# NOMIDI_Controller_006_clean.net
KiCad netlist of a schematic drawn in EAGLE
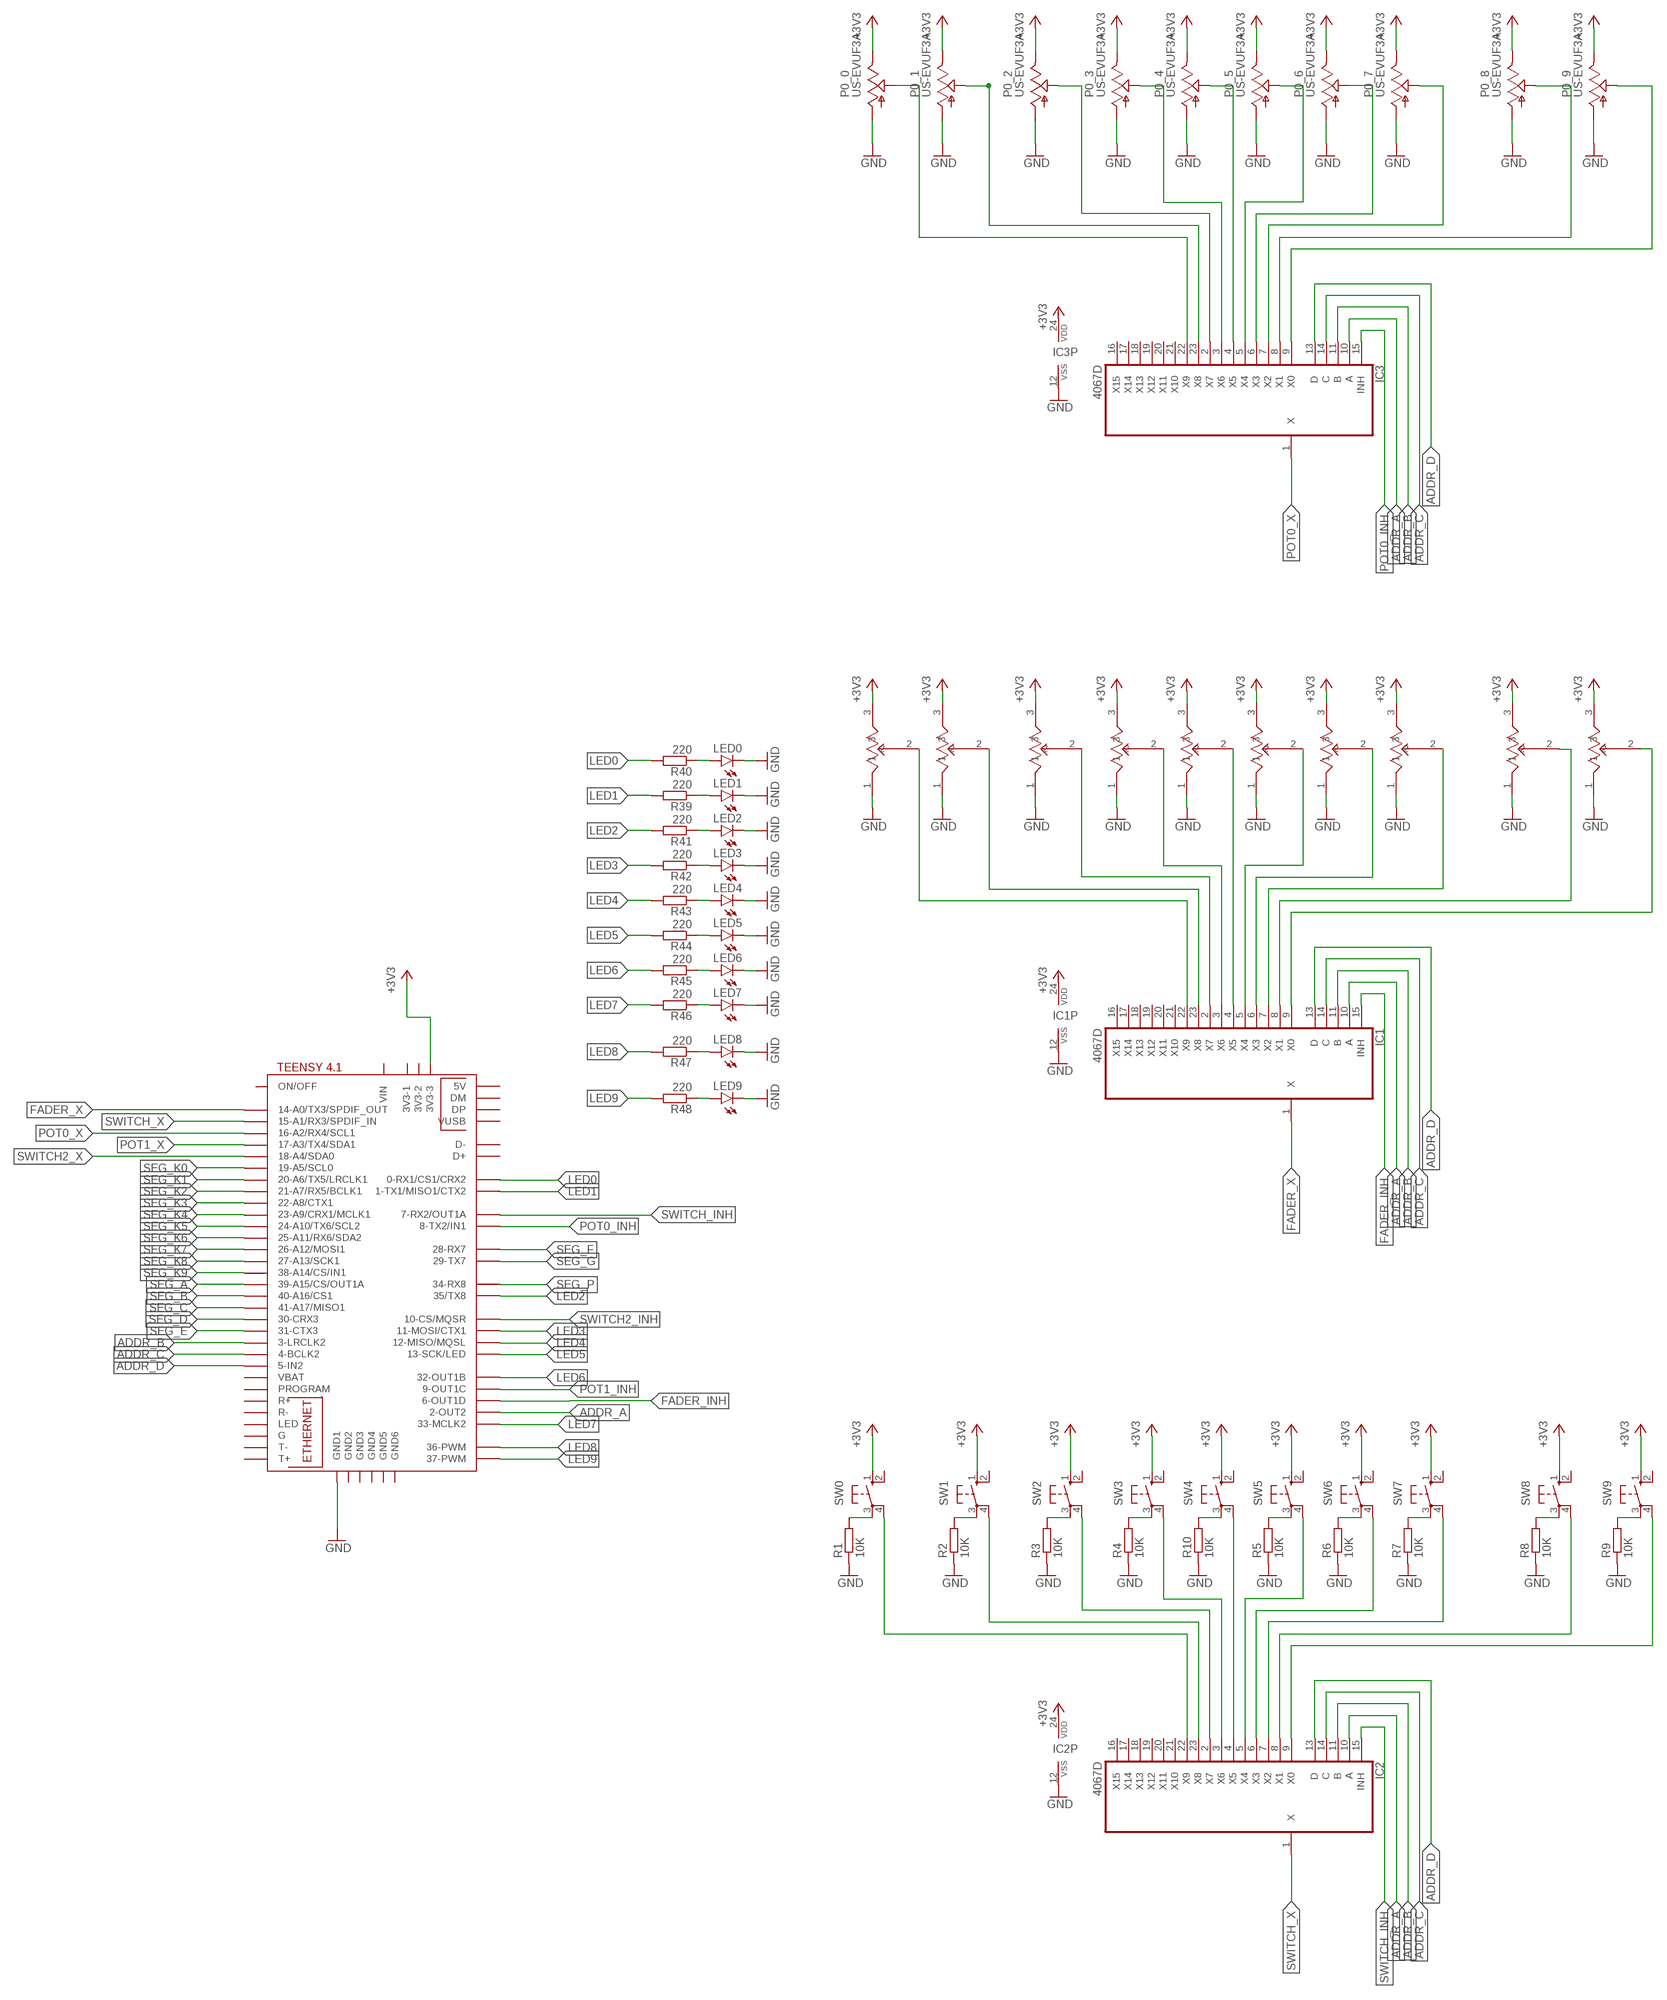
[diagram p0: schematic, sheet 1, part 1 of 3]
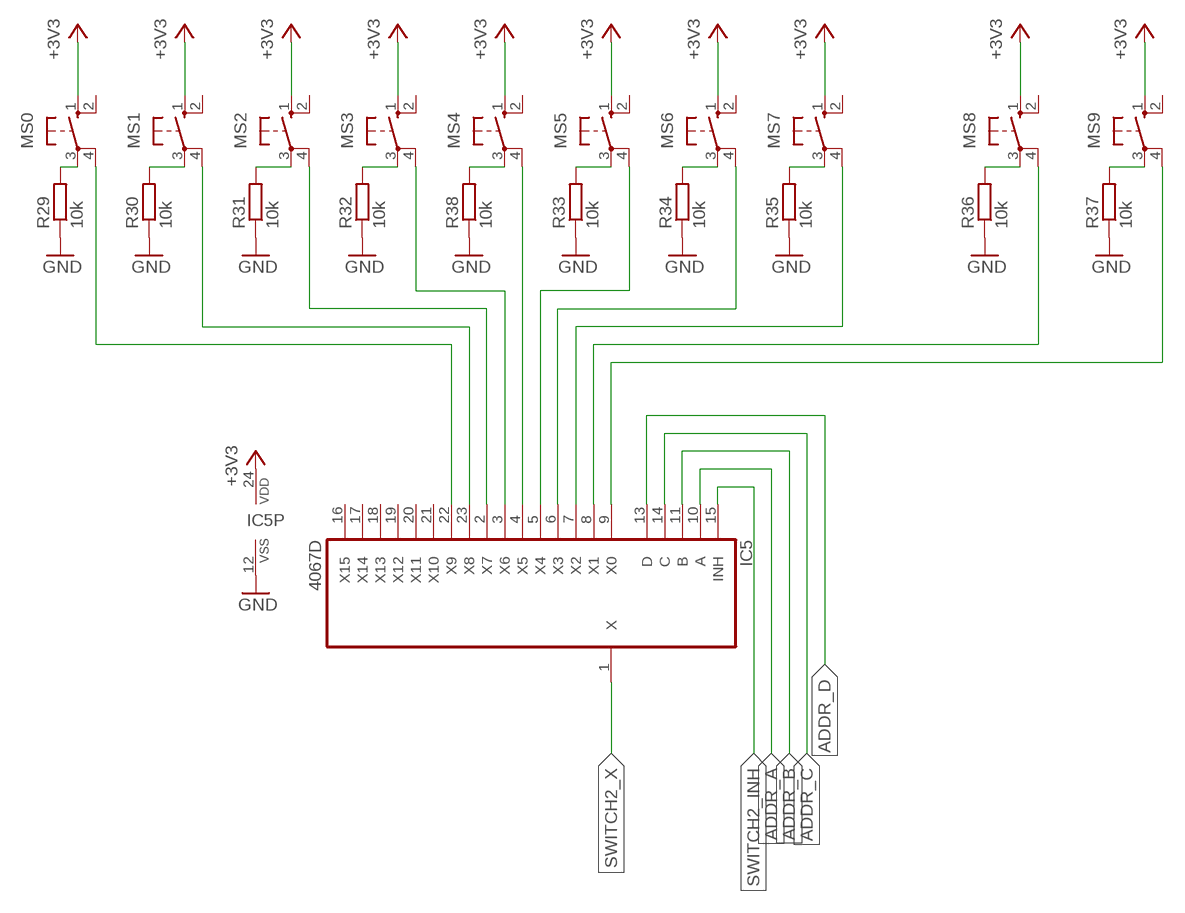
[diagram p1: schematic, sheet 1, part 2 of 3]
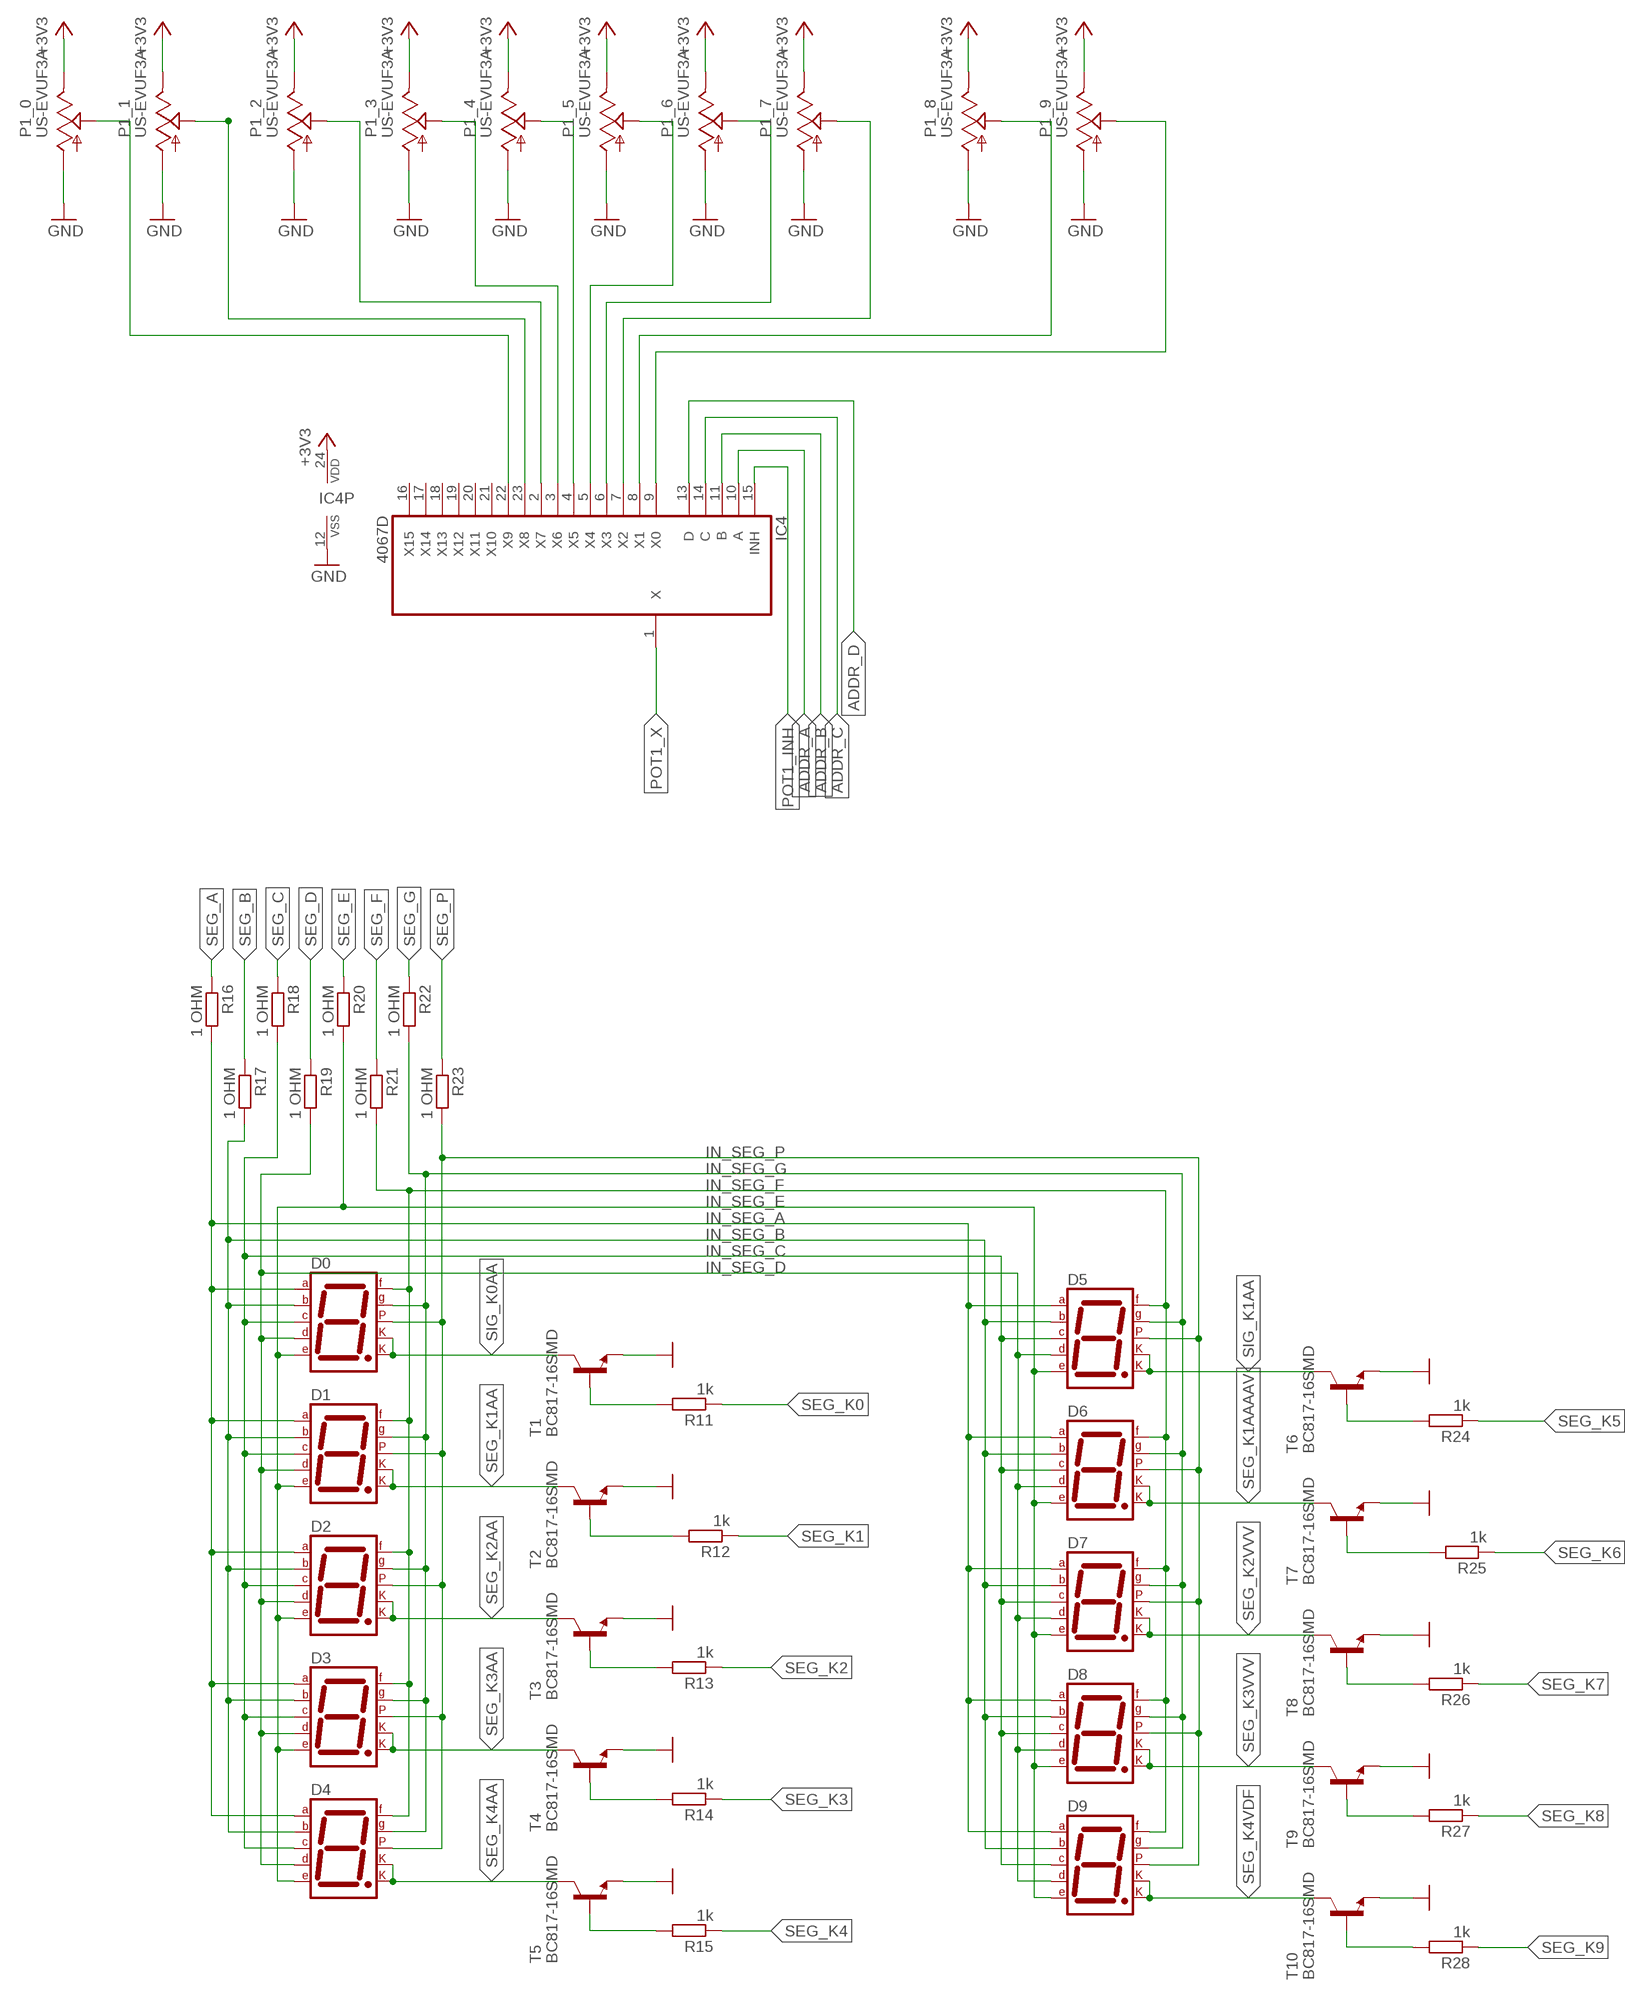
[diagram p2: schematic, sheet 1, part 3 of 3]

(export (version "E")
  (design (tool "Eeschema 10.0.6"))
  (components
    (comp (ref "D0")
      (value "7SEG-CK")
      (footprint "eagle-import:7SEG-13")
      (libsource (lib "eagle-import") (part "7SEG-CK"))
    )
    (comp (ref "D1")
      (value "7SEG-CK")
      (footprint "eagle-import:7SEG-13")
      (libsource (lib "eagle-import") (part "7SEG-CK"))
    )
    (comp (ref "D2")
      (value "7SEG-CK")
      (footprint "eagle-import:7SEG-13")
      (libsource (lib "eagle-import") (part "7SEG-CK"))
    )
    (comp (ref "D3")
      (value "7SEG-CK")
      (footprint "eagle-import:7SEG-13")
      (libsource (lib "eagle-import") (part "7SEG-CK"))
    )
    (comp (ref "D4")
      (value "7SEG-CK")
      (footprint "eagle-import:7SEG-13")
      (libsource (lib "eagle-import") (part "7SEG-CK"))
    )
    (comp (ref "D5")
      (value "7SEG-CK")
      (footprint "eagle-import:7SEG-13")
      (libsource (lib "eagle-import") (part "7SEG-CK"))
    )
    (comp (ref "D6")
      (value "7SEG-CK")
      (footprint "eagle-import:7SEG-13")
      (libsource (lib "eagle-import") (part "7SEG-CK"))
    )
    (comp (ref "D7")
      (value "7SEG-CK")
      (footprint "eagle-import:7SEG-13")
      (libsource (lib "eagle-import") (part "7SEG-CK"))
    )
    (comp (ref "D8")
      (value "7SEG-CK")
      (footprint "eagle-import:7SEG-13")
      (libsource (lib "eagle-import") (part "7SEG-CK"))
    )
    (comp (ref "D9")
      (value "7SEG-CK")
      (footprint "eagle-import:7SEG-13")
      (libsource (lib "eagle-import") (part "7SEG-CK"))
    )
    (comp (ref "IC1")
      (value "4067D")
      (footprint "eagle-import:SO24W")
      (libsource (lib "eagle-import") (part "4067D"))
    )
    (comp (ref "IC2")
      (value "4067D")
      (footprint "eagle-import:SO24W")
      (libsource (lib "eagle-import") (part "4067D"))
    )
    (comp (ref "IC3")
      (value "4067D")
      (footprint "eagle-import:SO24W")
      (libsource (lib "eagle-import") (part "4067D"))
    )
    (comp (ref "IC4")
      (value "4067D")
      (footprint "eagle-import:SO24W")
      (libsource (lib "eagle-import") (part "4067D"))
    )
    (comp (ref "IC5")
      (value "4067D")
      (footprint "eagle-import:SO24W")
      (libsource (lib "eagle-import") (part "4067D"))
    )
    (comp (ref "LED0")
      (value "LED3MM")
      (footprint "eagle-import:LED3MM")
      (libsource (lib "eagle-import") (part "LED3MM"))
    )
    (comp (ref "LED1")
      (value "LED3MM")
      (footprint "eagle-import:LED3MM")
      (libsource (lib "eagle-import") (part "LED3MM"))
    )
    (comp (ref "LED2")
      (value "LED3MM")
      (footprint "eagle-import:LED3MM")
      (libsource (lib "eagle-import") (part "LED3MM"))
    )
    (comp (ref "LED3")
      (value "LED3MM")
      (footprint "eagle-import:LED3MM")
      (libsource (lib "eagle-import") (part "LED3MM"))
    )
    (comp (ref "LED4")
      (value "LED3MM")
      (footprint "eagle-import:LED3MM")
      (libsource (lib "eagle-import") (part "LED3MM"))
    )
    (comp (ref "LED5")
      (value "LED3MM")
      (footprint "eagle-import:LED3MM")
      (libsource (lib "eagle-import") (part "LED3MM"))
    )
    (comp (ref "LED6")
      (value "LED3MM")
      (footprint "eagle-import:LED3MM")
      (libsource (lib "eagle-import") (part "LED3MM"))
    )
    (comp (ref "LED7")
      (value "LED3MM")
      (footprint "eagle-import:LED3MM")
      (libsource (lib "eagle-import") (part "LED3MM"))
    )
    (comp (ref "LED8")
      (value "LED3MM")
      (footprint "eagle-import:LED3MM")
      (libsource (lib "eagle-import") (part "LED3MM"))
    )
    (comp (ref "LED9")
      (value "LED3MM")
      (footprint "eagle-import:LED3MM")
      (libsource (lib "eagle-import") (part "LED3MM"))
    )
    (comp (ref "M0")
      (value "SLIDEPOT-ALPS-60MM")
      (footprint "eagle-import:RS6011SP600")
      (libsource (lib "eagle-import") (part "SLIDEPOT-ALPS-60MM"))
    )
    (comp (ref "M1")
      (value "SLIDEPOT-ALPS-60MM")
      (footprint "eagle-import:RS6011SP600")
      (libsource (lib "eagle-import") (part "SLIDEPOT-ALPS-60MM"))
    )
    (comp (ref "MS0")
      (value "10-XX")
      (footprint "eagle-import:B3F-10XX")
      (fields (field (name "MPN") "B3F-1000"))
      (libsource (lib "eagle-import") (part "10-XX"))
    )
    (comp (ref "MS1")
      (value "10-XX")
      (footprint "eagle-import:B3F-10XX")
      (fields (field (name "MPN") "B3F-1000"))
      (libsource (lib "eagle-import") (part "10-XX"))
    )
    (comp (ref "MS2")
      (value "10-XX")
      (footprint "eagle-import:B3F-10XX")
      (fields (field (name "MPN") "B3F-1000"))
      (libsource (lib "eagle-import") (part "10-XX"))
    )
    (comp (ref "MS3")
      (value "10-XX")
      (footprint "eagle-import:B3F-10XX")
      (fields (field (name "MPN") "B3F-1000"))
      (libsource (lib "eagle-import") (part "10-XX"))
    )
    (comp (ref "MS4")
      (value "10-XX")
      (footprint "eagle-import:B3F-10XX")
      (fields (field (name "MPN") "B3F-1000"))
      (libsource (lib "eagle-import") (part "10-XX"))
    )
    (comp (ref "MS5")
      (value "10-XX")
      (footprint "eagle-import:B3F-10XX")
      (fields (field (name "MPN") "B3F-1000"))
      (libsource (lib "eagle-import") (part "10-XX"))
    )
    (comp (ref "MS6")
      (value "10-XX")
      (footprint "eagle-import:B3F-10XX")
      (fields (field (name "MPN") "B3F-1000"))
      (libsource (lib "eagle-import") (part "10-XX"))
    )
    (comp (ref "MS7")
      (value "10-XX")
      (footprint "eagle-import:B3F-10XX")
      (fields (field (name "MPN") "B3F-1000"))
      (libsource (lib "eagle-import") (part "10-XX"))
    )
    (comp (ref "MS8")
      (value "10-XX")
      (footprint "eagle-import:B3F-10XX")
      (fields (field (name "MPN") "B3F-1000"))
      (libsource (lib "eagle-import") (part "10-XX"))
    )
    (comp (ref "MS9")
      (value "10-XX")
      (footprint "eagle-import:B3F-10XX")
      (fields (field (name "MPN") "B3F-1000"))
      (libsource (lib "eagle-import") (part "10-XX"))
    )
    (comp (ref "P0_0")
      (value "US-EVUF3A")
      (footprint "eagle-import:EVUF")
      (libsource (lib "eagle-import") (part "US-EVUAF3"))
    )
    (comp (ref "P0_1")
      (value "US-EVUF3A")
      (footprint "eagle-import:EVUF")
      (libsource (lib "eagle-import") (part "US-EVUAF3"))
    )
    (comp (ref "P0_2")
      (value "US-EVUF3A")
      (footprint "eagle-import:EVUF")
      (libsource (lib "eagle-import") (part "US-EVUAF3"))
    )
    (comp (ref "P0_3")
      (value "US-EVUF3A")
      (footprint "eagle-import:EVUF")
      (libsource (lib "eagle-import") (part "US-EVUAF3"))
    )
    (comp (ref "P0_4")
      (value "US-EVUF3A")
      (footprint "eagle-import:EVUF")
      (libsource (lib "eagle-import") (part "US-EVUAF3"))
    )
    (comp (ref "P0_5")
      (value "US-EVUF3A")
      (footprint "eagle-import:EVUF")
      (libsource (lib "eagle-import") (part "US-EVUAF3"))
    )
    (comp (ref "P0_6")
      (value "US-EVUF3A")
      (footprint "eagle-import:EVUF")
      (libsource (lib "eagle-import") (part "US-EVUAF3"))
    )
    (comp (ref "P0_7")
      (value "US-EVUF3A")
      (footprint "eagle-import:EVUF")
      (libsource (lib "eagle-import") (part "US-EVUAF3"))
    )
    (comp (ref "P0_8")
      (value "US-EVUF3A")
      (footprint "eagle-import:EVUF")
      (libsource (lib "eagle-import") (part "US-EVUAF3"))
    )
    (comp (ref "P0_9")
      (value "US-EVUF3A")
      (footprint "eagle-import:EVUF")
      (libsource (lib "eagle-import") (part "US-EVUAF3"))
    )
    (comp (ref "P1_0")
      (value "US-EVUF3A")
      (footprint "eagle-import:EVUF")
      (libsource (lib "eagle-import") (part "US-EVUAF3"))
    )
    (comp (ref "P1_1")
      (value "US-EVUF3A")
      (footprint "eagle-import:EVUF")
      (libsource (lib "eagle-import") (part "US-EVUAF3"))
    )
    (comp (ref "P1_2")
      (value "US-EVUF3A")
      (footprint "eagle-import:EVUF")
      (libsource (lib "eagle-import") (part "US-EVUAF3"))
    )
    (comp (ref "P1_3")
      (value "US-EVUF3A")
      (footprint "eagle-import:EVUF")
      (libsource (lib "eagle-import") (part "US-EVUAF3"))
    )
    (comp (ref "P1_4")
      (value "US-EVUF3A")
      (footprint "eagle-import:EVUF")
      (libsource (lib "eagle-import") (part "US-EVUAF3"))
    )
    (comp (ref "P1_5")
      (value "US-EVUF3A")
      (footprint "eagle-import:EVUF")
      (libsource (lib "eagle-import") (part "US-EVUAF3"))
    )
    (comp (ref "P1_6")
      (value "US-EVUF3A")
      (footprint "eagle-import:EVUF")
      (libsource (lib "eagle-import") (part "US-EVUAF3"))
    )
    (comp (ref "P1_7")
      (value "US-EVUF3A")
      (footprint "eagle-import:EVUF")
      (libsource (lib "eagle-import") (part "US-EVUAF3"))
    )
    (comp (ref "P1_8")
      (value "US-EVUF3A")
      (footprint "eagle-import:EVUF")
      (libsource (lib "eagle-import") (part "US-EVUAF3"))
    )
    (comp (ref "P1_9")
      (value "US-EVUF3A")
      (footprint "eagle-import:EVUF")
      (libsource (lib "eagle-import") (part "US-EVUAF3"))
    )
    (comp (ref "R1")
      (value "10K")
      (footprint "eagle-import:0207_7")
      (libsource (lib "eagle-import") (part "R-EU_0207/7"))
    )
    (comp (ref "R2")
      (value "10K")
      (footprint "eagle-import:0207_7")
      (libsource (lib "eagle-import") (part "R-EU_0207/7"))
    )
    (comp (ref "R3")
      (value "10K")
      (footprint "eagle-import:0207_7")
      (libsource (lib "eagle-import") (part "R-EU_0207/7"))
    )
    (comp (ref "R4")
      (value "10K")
      (footprint "eagle-import:0207_7")
      (libsource (lib "eagle-import") (part "R-EU_0207/7"))
    )
    (comp (ref "R5")
      (value "10K")
      (footprint "eagle-import:0207_7")
      (libsource (lib "eagle-import") (part "R-EU_0207/7"))
    )
    (comp (ref "R6")
      (value "10K")
      (footprint "eagle-import:0207_7")
      (libsource (lib "eagle-import") (part "R-EU_0207/7"))
    )
    (comp (ref "R7")
      (value "10K")
      (footprint "eagle-import:0207_7")
      (libsource (lib "eagle-import") (part "R-EU_0207/7"))
    )
    (comp (ref "R8")
      (value "10K")
      (footprint "eagle-import:0207_7")
      (libsource (lib "eagle-import") (part "R-EU_0207/7"))
    )
    (comp (ref "R9")
      (value "10K")
      (footprint "eagle-import:0207_7")
      (libsource (lib "eagle-import") (part "R-EU_0207/7"))
    )
    (comp (ref "R10")
      (value "10K")
      (footprint "eagle-import:0207_7")
      (libsource (lib "eagle-import") (part "R-EU_0207/7"))
    )
    (comp (ref "R11")
      (value "1k")
      (footprint "eagle-import:0207_7")
      (libsource (lib "eagle-import") (part "R-EU_0207/7"))
    )
    (comp (ref "R12")
      (value "1k")
      (footprint "eagle-import:0207_7")
      (libsource (lib "eagle-import") (part "R-EU_0207/7"))
    )
    (comp (ref "R13")
      (value "1k")
      (footprint "eagle-import:0207_7")
      (libsource (lib "eagle-import") (part "R-EU_0207/7"))
    )
    (comp (ref "R14")
      (value "1k")
      (footprint "eagle-import:0207_7")
      (libsource (lib "eagle-import") (part "R-EU_0207/7"))
    )
    (comp (ref "R15")
      (value "1k")
      (footprint "eagle-import:0207_7")
      (libsource (lib "eagle-import") (part "R-EU_0207/7"))
    )
    (comp (ref "R16")
      (value "1 OHM")
      (footprint "eagle-import:0207_7")
      (libsource (lib "eagle-import") (part "R-EU_0207/7"))
    )
    (comp (ref "R17")
      (value "1 OHM")
      (footprint "eagle-import:0207_7")
      (libsource (lib "eagle-import") (part "R-EU_0207/7"))
    )
    (comp (ref "R18")
      (value "1 OHM")
      (footprint "eagle-import:0207_7")
      (libsource (lib "eagle-import") (part "R-EU_0207/7"))
    )
    (comp (ref "R19")
      (value "1 OHM")
      (footprint "eagle-import:0207_7")
      (libsource (lib "eagle-import") (part "R-EU_0207/7"))
    )
    (comp (ref "R20")
      (value "1 OHM")
      (footprint "eagle-import:0207_7")
      (libsource (lib "eagle-import") (part "R-EU_0207/7"))
    )
    (comp (ref "R21")
      (value "1 OHM")
      (footprint "eagle-import:0207_7")
      (libsource (lib "eagle-import") (part "R-EU_0207/7"))
    )
    (comp (ref "R22")
      (value "1 OHM")
      (footprint "eagle-import:0207_7")
      (libsource (lib "eagle-import") (part "R-EU_0207/7"))
    )
    (comp (ref "R23")
      (value "1 OHM")
      (footprint "eagle-import:0207_7")
      (libsource (lib "eagle-import") (part "R-EU_0207/7"))
    )
    (comp (ref "R24")
      (value "1k")
      (footprint "eagle-import:0207_7")
      (libsource (lib "eagle-import") (part "R-EU_0207/7"))
    )
    (comp (ref "R25")
      (value "1k")
      (footprint "eagle-import:0207_7")
      (libsource (lib "eagle-import") (part "R-EU_0207/7"))
    )
    (comp (ref "R26")
      (value "1k")
      (footprint "eagle-import:0207_7")
      (libsource (lib "eagle-import") (part "R-EU_0207/7"))
    )
    (comp (ref "R27")
      (value "1k")
      (footprint "eagle-import:0207_7")
      (libsource (lib "eagle-import") (part "R-EU_0207/7"))
    )
    (comp (ref "R28")
      (value "1k")
      (footprint "eagle-import:0207_7")
      (libsource (lib "eagle-import") (part "R-EU_0207/7"))
    )
    (comp (ref "R29")
      (value "10k")
      (footprint "eagle-import:0207_7")
      (libsource (lib "eagle-import") (part "R-EU_0207/7"))
    )
    (comp (ref "R30")
      (value "10k")
      (footprint "eagle-import:0207_7")
      (libsource (lib "eagle-import") (part "R-EU_0207/7"))
    )
    (comp (ref "R31")
      (value "10k")
      (footprint "eagle-import:0207_7")
      (libsource (lib "eagle-import") (part "R-EU_0207/7"))
    )
    (comp (ref "R32")
      (value "10k")
      (footprint "eagle-import:0207_7")
      (libsource (lib "eagle-import") (part "R-EU_0207/7"))
    )
    (comp (ref "R33")
      (value "10k")
      (footprint "eagle-import:0207_7")
      (libsource (lib "eagle-import") (part "R-EU_0207/7"))
    )
    (comp (ref "R34")
      (value "10k")
      (footprint "eagle-import:0207_7")
      (libsource (lib "eagle-import") (part "R-EU_0207/7"))
    )
    (comp (ref "R35")
      (value "10k")
      (footprint "eagle-import:0207_7")
      (libsource (lib "eagle-import") (part "R-EU_0207/7"))
    )
    (comp (ref "R36")
      (value "10k")
      (footprint "eagle-import:0207_7")
      (libsource (lib "eagle-import") (part "R-EU_0207/7"))
    )
    (comp (ref "R37")
      (value "10k")
      (footprint "eagle-import:0207_7")
      (libsource (lib "eagle-import") (part "R-EU_0207/7"))
    )
    (comp (ref "R38")
      (value "10k")
      (footprint "eagle-import:0207_7")
      (libsource (lib "eagle-import") (part "R-EU_0207/7"))
    )
    (comp (ref "R39")
      (value "220")
      (footprint "eagle-import:0207_7")
      (libsource (lib "eagle-import") (part "R-EU_0207/7"))
    )
    (comp (ref "R40")
      (value "220")
      (footprint "eagle-import:0207_7")
      (libsource (lib "eagle-import") (part "R-EU_0207/7"))
    )
    (comp (ref "R41")
      (value "220")
      (footprint "eagle-import:0207_7")
      (libsource (lib "eagle-import") (part "R-EU_0207/7"))
    )
    (comp (ref "R42")
      (value "220")
      (footprint "eagle-import:0207_7")
      (libsource (lib "eagle-import") (part "R-EU_0207/7"))
    )
    (comp (ref "R43")
      (value "220")
      (footprint "eagle-import:0207_7")
      (libsource (lib "eagle-import") (part "R-EU_0207/7"))
    )
    (comp (ref "R44")
      (value "220")
      (footprint "eagle-import:0207_7")
      (libsource (lib "eagle-import") (part "R-EU_0207/7"))
    )
    (comp (ref "R45")
      (value "220")
      (footprint "eagle-import:0207_7")
      (libsource (lib "eagle-import") (part "R-EU_0207/7"))
    )
    (comp (ref "R46")
      (value "220")
      (footprint "eagle-import:0207_7")
      (libsource (lib "eagle-import") (part "R-EU_0207/7"))
    )
    (comp (ref "R47")
      (value "220")
      (footprint "eagle-import:0207_7")
      (libsource (lib "eagle-import") (part "R-EU_0207/7"))
    )
    (comp (ref "R48")
      (value "220")
      (footprint "eagle-import:0207_7")
      (libsource (lib "eagle-import") (part "R-EU_0207/7"))
    )
    (comp (ref "S0")
      (value "SLIDEPOT-ALPS-60MM")
      (footprint "eagle-import:RS6011SP600")
      (libsource (lib "eagle-import") (part "SLIDEPOT-ALPS-60MM"))
    )
    (comp (ref "S1")
      (value "SLIDEPOT-ALPS-60MM")
      (footprint "eagle-import:RS6011SP600")
      (libsource (lib "eagle-import") (part "SLIDEPOT-ALPS-60MM"))
    )
    (comp (ref "S2")
      (value "SLIDEPOT-ALPS-60MM")
      (footprint "eagle-import:RS6011SP600")
      (libsource (lib "eagle-import") (part "SLIDEPOT-ALPS-60MM"))
    )
    (comp (ref "S3")
      (value "SLIDEPOT-ALPS-60MM")
      (footprint "eagle-import:RS6011SP600")
      (libsource (lib "eagle-import") (part "SLIDEPOT-ALPS-60MM"))
    )
    (comp (ref "S4")
      (value "SLIDEPOT-ALPS-60MM")
      (footprint "eagle-import:RS6011SP600")
      (libsource (lib "eagle-import") (part "SLIDEPOT-ALPS-60MM"))
    )
    (comp (ref "S5")
      (value "SLIDEPOT-ALPS-60MM")
      (footprint "eagle-import:RS6011SP600")
      (libsource (lib "eagle-import") (part "SLIDEPOT-ALPS-60MM"))
    )
    (comp (ref "S6")
      (value "SLIDEPOT-ALPS-60MM")
      (footprint "eagle-import:RS6011SP600")
      (libsource (lib "eagle-import") (part "SLIDEPOT-ALPS-60MM"))
    )
    (comp (ref "S7")
      (value "SLIDEPOT-ALPS-60MM")
      (footprint "eagle-import:RS6011SP600")
      (libsource (lib "eagle-import") (part "SLIDEPOT-ALPS-60MM"))
    )
    (comp (ref "SW0")
      (value "10-XX")
      (footprint "eagle-import:B3F-10XX")
      (fields (field (name "MPN") "B3F-1000"))
      (libsource (lib "eagle-import") (part "10-XX"))
    )
    (comp (ref "SW1")
      (value "10-XX")
      (footprint "eagle-import:B3F-10XX")
      (fields (field (name "MPN") "B3F-1000"))
      (libsource (lib "eagle-import") (part "10-XX"))
    )
    (comp (ref "SW2")
      (value "10-XX")
      (footprint "eagle-import:B3F-10XX")
      (fields (field (name "MPN") "B3F-1000"))
      (libsource (lib "eagle-import") (part "10-XX"))
    )
    (comp (ref "SW3")
      (value "10-XX")
      (footprint "eagle-import:B3F-10XX")
      (fields (field (name "MPN") "B3F-1000"))
      (libsource (lib "eagle-import") (part "10-XX"))
    )
    (comp (ref "SW4")
      (value "10-XX")
      (footprint "eagle-import:B3F-10XX")
      (fields (field (name "MPN") "B3F-1000"))
      (libsource (lib "eagle-import") (part "10-XX"))
    )
    (comp (ref "SW5")
      (value "10-XX")
      (footprint "eagle-import:B3F-10XX")
      (fields (field (name "MPN") "B3F-1000"))
      (libsource (lib "eagle-import") (part "10-XX"))
    )
    (comp (ref "SW6")
      (value "10-XX")
      (footprint "eagle-import:B3F-10XX")
      (fields (field (name "MPN") "B3F-1000"))
      (libsource (lib "eagle-import") (part "10-XX"))
    )
    (comp (ref "SW7")
      (value "10-XX")
      (footprint "eagle-import:B3F-10XX")
      (fields (field (name "MPN") "B3F-1000"))
      (libsource (lib "eagle-import") (part "10-XX"))
    )
    (comp (ref "SW8")
      (value "10-XX")
      (footprint "eagle-import:B3F-10XX")
      (fields (field (name "MPN") "B3F-1000"))
      (libsource (lib "eagle-import") (part "10-XX"))
    )
    (comp (ref "SW9")
      (value "10-XX")
      (footprint "eagle-import:B3F-10XX")
      (fields (field (name "MPN") "B3F-1000"))
      (libsource (lib "eagle-import") (part "10-XX"))
    )
    (comp (ref "T1")
      (value "BC817-16SMD")
      (footprint "eagle-import:SOT23-BEC")
      (libsource (lib "eagle-import") (part "BC817SMD-16"))
    )
    (comp (ref "T2")
      (value "BC817-16SMD")
      (footprint "eagle-import:SOT23-BEC")
      (libsource (lib "eagle-import") (part "BC817SMD-16"))
    )
    (comp (ref "T3")
      (value "BC817-16SMD")
      (footprint "eagle-import:SOT23-BEC")
      (libsource (lib "eagle-import") (part "BC817SMD-16"))
    )
    (comp (ref "T4")
      (value "BC817-16SMD")
      (footprint "eagle-import:SOT23-BEC")
      (libsource (lib "eagle-import") (part "BC817SMD-16"))
    )
    (comp (ref "T5")
      (value "BC817-16SMD")
      (footprint "eagle-import:SOT23-BEC")
      (libsource (lib "eagle-import") (part "BC817SMD-16"))
    )
    (comp (ref "T6")
      (value "BC817-16SMD")
      (footprint "eagle-import:SOT23-BEC")
      (libsource (lib "eagle-import") (part "BC817SMD-16"))
    )
    (comp (ref "T7")
      (value "BC817-16SMD")
      (footprint "eagle-import:SOT23-BEC")
      (libsource (lib "eagle-import") (part "BC817SMD-16"))
    )
    (comp (ref "T8")
      (value "BC817-16SMD")
      (footprint "eagle-import:SOT23-BEC")
      (libsource (lib "eagle-import") (part "BC817SMD-16"))
    )
    (comp (ref "T9")
      (value "BC817-16SMD")
      (footprint "eagle-import:SOT23-BEC")
      (libsource (lib "eagle-import") (part "BC817SMD-16"))
    )
    (comp (ref "T10")
      (value "BC817-16SMD")
      (footprint "eagle-import:SOT23-BEC")
      (libsource (lib "eagle-import") (part "BC817SMD-16"))
    )
    (comp (ref "U$1")
      (value "TEENSY41")
      (footprint "eagle-import:TEENSY41")
      (libsource (lib "eagle-import") (part "TEENSY41"))
    )
  )
  (nets
    (net (code "1") (name "+3V3") (class "Default")
      (node (ref "IC1") (pin "24") (pinfunction "VDD_24") (pintype "power_in"))
      (node (ref "IC2") (pin "24") (pinfunction "VDD_24") (pintype "power_in"))
      (node (ref "IC3") (pin "24") (pinfunction "VDD_24") (pintype "power_in"))
      (node (ref "IC4") (pin "24") (pinfunction "VDD_24") (pintype "power_in"))
      (node (ref "IC5") (pin "24") (pinfunction "VDD_24") (pintype "power_in"))
      (node (ref "M0") (pin "3") (pinfunction "3_3") (pintype "bidirectional"))
      (node (ref "M1") (pin "3") (pinfunction "3_3") (pintype "bidirectional"))
      (node (ref "MS0") (pin "1") (pinfunction "S_1") (pintype "passive"))
      (node (ref "MS1") (pin "1") (pinfunction "S_1") (pintype "passive"))
      (node (ref "MS2") (pin "1") (pinfunction "S_1") (pintype "passive"))
      (node (ref "MS3") (pin "1") (pinfunction "S_1") (pintype "passive"))
      (node (ref "MS4") (pin "1") (pinfunction "S_1") (pintype "passive"))
      (node (ref "MS5") (pin "1") (pinfunction "S_1") (pintype "passive"))
      (node (ref "MS6") (pin "1") (pinfunction "S_1") (pintype "passive"))
      (node (ref "MS7") (pin "1") (pinfunction "S_1") (pintype "passive"))
      (node (ref "MS8") (pin "1") (pinfunction "S_1") (pintype "passive"))
      (node (ref "MS9") (pin "1") (pinfunction "S_1") (pintype "passive"))
      (node (ref "P0_0") (pin "3") (pinfunction "E_3") (pintype "passive"))
      (node (ref "P0_1") (pin "3") (pinfunction "E_3") (pintype "passive"))
      (node (ref "P0_2") (pin "3") (pinfunction "E_3") (pintype "passive"))
      (node (ref "P0_3") (pin "3") (pinfunction "E_3") (pintype "passive"))
      (node (ref "P0_4") (pin "3") (pinfunction "E_3") (pintype "passive"))
      (node (ref "P0_5") (pin "3") (pinfunction "E_3") (pintype "passive"))
      (node (ref "P0_6") (pin "3") (pinfunction "E_3") (pintype "passive"))
      (node (ref "P0_7") (pin "3") (pinfunction "E_3") (pintype "passive"))
      (node (ref "P0_8") (pin "3") (pinfunction "E_3") (pintype "passive"))
      (node (ref "P0_9") (pin "3") (pinfunction "E_3") (pintype "passive"))
      (node (ref "P1_0") (pin "3") (pinfunction "E_3") (pintype "passive"))
      (node (ref "P1_1") (pin "3") (pinfunction "E_3") (pintype "passive"))
      (node (ref "P1_2") (pin "3") (pinfunction "E_3") (pintype "passive"))
      (node (ref "P1_3") (pin "3") (pinfunction "E_3") (pintype "passive"))
      (node (ref "P1_4") (pin "3") (pinfunction "E_3") (pintype "passive"))
      (node (ref "P1_5") (pin "3") (pinfunction "E_3") (pintype "passive"))
      (node (ref "P1_6") (pin "3") (pinfunction "E_3") (pintype "passive"))
      (node (ref "P1_7") (pin "3") (pinfunction "E_3") (pintype "passive"))
      (node (ref "P1_8") (pin "3") (pinfunction "E_3") (pintype "passive"))
      (node (ref "P1_9") (pin "3") (pinfunction "E_3") (pintype "passive"))
      (node (ref "S0") (pin "3") (pinfunction "3_3") (pintype "bidirectional"))
      (node (ref "S1") (pin "3") (pinfunction "3_3") (pintype "bidirectional"))
      (node (ref "S2") (pin "3") (pinfunction "3_3") (pintype "bidirectional"))
      (node (ref "S3") (pin "3") (pinfunction "3_3") (pintype "bidirectional"))
      (node (ref "S4") (pin "3") (pinfunction "3_3") (pintype "bidirectional"))
      (node (ref "S5") (pin "3") (pinfunction "3_3") (pintype "bidirectional"))
      (node (ref "S6") (pin "3") (pinfunction "3_3") (pintype "bidirectional"))
      (node (ref "S7") (pin "3") (pinfunction "3_3") (pintype "bidirectional"))
      (node (ref "SW0") (pin "1") (pinfunction "S_1") (pintype "passive"))
      (node (ref "SW1") (pin "1") (pinfunction "S_1") (pintype "passive"))
      (node (ref "SW2") (pin "1") (pinfunction "S_1") (pintype "passive"))
      (node (ref "SW3") (pin "1") (pinfunction "S_1") (pintype "passive"))
      (node (ref "SW4") (pin "1") (pinfunction "S_1") (pintype "passive"))
      (node (ref "SW5") (pin "1") (pinfunction "S_1") (pintype "passive"))
      (node (ref "SW6") (pin "1") (pinfunction "S_1") (pintype "passive"))
      (node (ref "SW7") (pin "1") (pinfunction "S_1") (pintype "passive"))
      (node (ref "SW8") (pin "1") (pinfunction "S_1") (pintype "passive"))
      (node (ref "SW9") (pin "1") (pinfunction "S_1") (pintype "passive"))
      (node (ref "U$1") (pin "3V3-3") (pinfunction "3V3-3_3V3-3") (pintype "bidirectional"))
    )
    (net (code "2") (name "/IN_SEG_A") (class "Default")
      (node (ref "D0") (pin "7") (pinfunction "A_7") (pintype "passive"))
      (node (ref "D1") (pin "7") (pinfunction "A_7") (pintype "passive"))
      (node (ref "D2") (pin "7") (pinfunction "A_7") (pintype "passive"))
      (node (ref "D3") (pin "7") (pinfunction "A_7") (pintype "passive"))
      (node (ref "D4") (pin "7") (pinfunction "A_7") (pintype "passive"))
      (node (ref "D5") (pin "7") (pinfunction "A_7") (pintype "passive"))
      (node (ref "D6") (pin "7") (pinfunction "A_7") (pintype "passive"))
      (node (ref "D7") (pin "7") (pinfunction "A_7") (pintype "passive"))
      (node (ref "D8") (pin "7") (pinfunction "A_7") (pintype "passive"))
      (node (ref "D9") (pin "7") (pinfunction "A_7") (pintype "passive"))
      (node (ref "R16") (pin "2") (pinfunction "2_2") (pintype "passive"))
    )
    (net (code "3") (name "/IN_SEG_B") (class "Default")
      (node (ref "D0") (pin "6") (pinfunction "B_6") (pintype "passive"))
      (node (ref "D1") (pin "6") (pinfunction "B_6") (pintype "passive"))
      (node (ref "D2") (pin "6") (pinfunction "B_6") (pintype "passive"))
      (node (ref "D3") (pin "6") (pinfunction "B_6") (pintype "passive"))
      (node (ref "D4") (pin "6") (pinfunction "B_6") (pintype "passive"))
      (node (ref "D5") (pin "6") (pinfunction "B_6") (pintype "passive"))
      (node (ref "D6") (pin "6") (pinfunction "B_6") (pintype "passive"))
      (node (ref "D7") (pin "6") (pinfunction "B_6") (pintype "passive"))
      (node (ref "D8") (pin "6") (pinfunction "B_6") (pintype "passive"))
      (node (ref "D9") (pin "6") (pinfunction "B_6") (pintype "passive"))
      (node (ref "R17") (pin "2") (pinfunction "2_2") (pintype "passive"))
    )
    (net (code "4") (name "/IN_SEG_C") (class "Default")
      (node (ref "D0") (pin "4") (pinfunction "C_4") (pintype "passive"))
      (node (ref "D1") (pin "4") (pinfunction "C_4") (pintype "passive"))
      (node (ref "D2") (pin "4") (pinfunction "C_4") (pintype "passive"))
      (node (ref "D3") (pin "4") (pinfunction "C_4") (pintype "passive"))
      (node (ref "D4") (pin "4") (pinfunction "C_4") (pintype "passive"))
      (node (ref "D5") (pin "4") (pinfunction "C_4") (pintype "passive"))
      (node (ref "D6") (pin "4") (pinfunction "C_4") (pintype "passive"))
      (node (ref "D7") (pin "4") (pinfunction "C_4") (pintype "passive"))
      (node (ref "D8") (pin "4") (pinfunction "C_4") (pintype "passive"))
      (node (ref "D9") (pin "4") (pinfunction "C_4") (pintype "passive"))
      (node (ref "R18") (pin "2") (pinfunction "2_2") (pintype "passive"))
    )
    (net (code "5") (name "/IN_SEG_D") (class "Default")
      (node (ref "D0") (pin "2") (pinfunction "D_2") (pintype "passive"))
      (node (ref "D1") (pin "2") (pinfunction "D_2") (pintype "passive"))
      (node (ref "D2") (pin "2") (pinfunction "D_2") (pintype "passive"))
      (node (ref "D3") (pin "2") (pinfunction "D_2") (pintype "passive"))
      (node (ref "D4") (pin "2") (pinfunction "D_2") (pintype "passive"))
      (node (ref "D5") (pin "2") (pinfunction "D_2") (pintype "passive"))
      (node (ref "D6") (pin "2") (pinfunction "D_2") (pintype "passive"))
      (node (ref "D7") (pin "2") (pinfunction "D_2") (pintype "passive"))
      (node (ref "D8") (pin "2") (pinfunction "D_2") (pintype "passive"))
      (node (ref "D9") (pin "2") (pinfunction "D_2") (pintype "passive"))
      (node (ref "R19") (pin "2") (pinfunction "2_2") (pintype "passive"))
    )
    (net (code "6") (name "/IN_SEG_E") (class "Default")
      (node (ref "D0") (pin "1") (pinfunction "E_1") (pintype "passive"))
      (node (ref "D1") (pin "1") (pinfunction "E_1") (pintype "passive"))
      (node (ref "D2") (pin "1") (pinfunction "E_1") (pintype "passive"))
      (node (ref "D3") (pin "1") (pinfunction "E_1") (pintype "passive"))
      (node (ref "D4") (pin "1") (pinfunction "E_1") (pintype "passive"))
      (node (ref "D5") (pin "1") (pinfunction "E_1") (pintype "passive"))
      (node (ref "D6") (pin "1") (pinfunction "E_1") (pintype "passive"))
      (node (ref "D7") (pin "1") (pinfunction "E_1") (pintype "passive"))
      (node (ref "D8") (pin "1") (pinfunction "E_1") (pintype "passive"))
      (node (ref "D9") (pin "1") (pinfunction "E_1") (pintype "passive"))
      (node (ref "R20") (pin "2") (pinfunction "2_2") (pintype "passive"))
    )
    (net (code "7") (name "/IN_SEG_F") (class "Default")
      (node (ref "D0") (pin "9") (pinfunction "F_9") (pintype "passive"))
      (node (ref "D1") (pin "9") (pinfunction "F_9") (pintype "passive"))
      (node (ref "D2") (pin "9") (pinfunction "F_9") (pintype "passive"))
      (node (ref "D3") (pin "9") (pinfunction "F_9") (pintype "passive"))
      (node (ref "D4") (pin "9") (pinfunction "F_9") (pintype "passive"))
      (node (ref "D5") (pin "9") (pinfunction "F_9") (pintype "passive"))
      (node (ref "D6") (pin "9") (pinfunction "F_9") (pintype "passive"))
      (node (ref "D7") (pin "9") (pinfunction "F_9") (pintype "passive"))
      (node (ref "D8") (pin "9") (pinfunction "F_9") (pintype "passive"))
      (node (ref "D9") (pin "9") (pinfunction "F_9") (pintype "passive"))
      (node (ref "R21") (pin "2") (pinfunction "2_2") (pintype "passive"))
    )
    (net (code "8") (name "/IN_SEG_G") (class "Default")
      (node (ref "D0") (pin "10") (pinfunction "G_10") (pintype "passive"))
      (node (ref "D1") (pin "10") (pinfunction "G_10") (pintype "passive"))
      (node (ref "D2") (pin "10") (pinfunction "G_10") (pintype "passive"))
      (node (ref "D3") (pin "10") (pinfunction "G_10") (pintype "passive"))
      (node (ref "D4") (pin "10") (pinfunction "G_10") (pintype "passive"))
      (node (ref "D5") (pin "10") (pinfunction "G_10") (pintype "passive"))
      (node (ref "D6") (pin "10") (pinfunction "G_10") (pintype "passive"))
      (node (ref "D7") (pin "10") (pinfunction "G_10") (pintype "passive"))
      (node (ref "D8") (pin "10") (pinfunction "G_10") (pintype "passive"))
      (node (ref "D9") (pin "10") (pinfunction "G_10") (pintype "passive"))
      (node (ref "R22") (pin "2") (pinfunction "2_2") (pintype "passive"))
    )
    (net (code "9") (name "/IN_SEG_P") (class "Default")
      (node (ref "D0") (pin "5") (pinfunction "DP_5") (pintype "passive"))
      (node (ref "D1") (pin "5") (pinfunction "DP_5") (pintype "passive"))
      (node (ref "D2") (pin "5") (pinfunction "DP_5") (pintype "passive"))
      (node (ref "D3") (pin "5") (pinfunction "DP_5") (pintype "passive"))
      (node (ref "D4") (pin "5") (pinfunction "DP_5") (pintype "passive"))
      (node (ref "D5") (pin "5") (pinfunction "DP_5") (pintype "passive"))
      (node (ref "D6") (pin "5") (pinfunction "DP_5") (pintype "passive"))
      (node (ref "D7") (pin "5") (pinfunction "DP_5") (pintype "passive"))
      (node (ref "D8") (pin "5") (pinfunction "DP_5") (pintype "passive"))
      (node (ref "D9") (pin "5") (pinfunction "DP_5") (pintype "passive"))
      (node (ref "R23") (pin "2") (pinfunction "2_2") (pintype "passive"))
    )
    (net (code "10") (name "ADDR_A") (class "Default")
      (node (ref "IC1") (pin "10") (pinfunction "A_10") (pintype "input"))
      (node (ref "IC2") (pin "10") (pinfunction "A_10") (pintype "input"))
      (node (ref "IC3") (pin "10") (pinfunction "A_10") (pintype "input"))
      (node (ref "IC4") (pin "10") (pinfunction "A_10") (pintype "input"))
      (node (ref "IC5") (pin "10") (pinfunction "A_10") (pintype "input"))
      (node (ref "U$1") (pin "2-OUT2") (pinfunction "2-OUT2_2-OUT2") (pintype "bidirectional"))
    )
    (net (code "11") (name "ADDR_B") (class "Default")
      (node (ref "IC1") (pin "11") (pinfunction "B_11") (pintype "input"))
      (node (ref "IC2") (pin "11") (pinfunction "B_11") (pintype "input"))
      (node (ref "IC3") (pin "11") (pinfunction "B_11") (pintype "input"))
      (node (ref "IC4") (pin "11") (pinfunction "B_11") (pintype "input"))
      (node (ref "IC5") (pin "11") (pinfunction "B_11") (pintype "input"))
      (node (ref "U$1") (pin "3-LRCLK2") (pinfunction "3-LRCLK2_3-LRCLK2") (pintype "bidirectional"))
    )
    (net (code "12") (name "ADDR_C") (class "Default")
      (node (ref "IC1") (pin "14") (pinfunction "C_14") (pintype "input"))
      (node (ref "IC2") (pin "14") (pinfunction "C_14") (pintype "input"))
      (node (ref "IC3") (pin "14") (pinfunction "C_14") (pintype "input"))
      (node (ref "IC4") (pin "14") (pinfunction "C_14") (pintype "input"))
      (node (ref "IC5") (pin "14") (pinfunction "C_14") (pintype "input"))
      (node (ref "U$1") (pin "4-BCLK2") (pinfunction "4-BCLK2_4-BCLK2") (pintype "bidirectional"))
    )
    (net (code "13") (name "ADDR_D") (class "Default")
      (node (ref "IC1") (pin "13") (pinfunction "D_13") (pintype "input"))
      (node (ref "IC2") (pin "13") (pinfunction "D_13") (pintype "input"))
      (node (ref "IC3") (pin "13") (pinfunction "D_13") (pintype "input"))
      (node (ref "IC4") (pin "13") (pinfunction "D_13") (pintype "input"))
      (node (ref "IC5") (pin "13") (pinfunction "D_13") (pintype "input"))
      (node (ref "U$1") (pin "5-IN2") (pinfunction "5-IN2_5-IN2") (pintype "bidirectional"))
    )
    (net (code "14") (name "FADER_INH") (class "Default")
      (node (ref "IC1") (pin "15") (pinfunction "INH_15") (pintype "input"))
      (node (ref "U$1") (pin "6-OUT1D") (pinfunction "6-OUT1D_6-OUT1D") (pintype "bidirectional"))
    )
    (net (code "15") (name "FADER_X") (class "Default")
      (node (ref "IC1") (pin "1") (pinfunction "X_1") (pintype "output"))
      (node (ref "U$1") (pin "14-A0/TX3/SPDIF_OUT") (pinfunction "14-A0/TX3/SPDIF_OUT_14-A0/TX3/SPDIF_OUT") (pintype "bidirectional"))
    )
    (net (code "16") (name "GND") (class "Default")
      (node (ref "IC1") (pin "12") (pinfunction "VSS_12") (pintype "power_in"))
      (node (ref "IC2") (pin "12") (pinfunction "VSS_12") (pintype "power_in"))
      (node (ref "IC3") (pin "12") (pinfunction "VSS_12") (pintype "power_in"))
      (node (ref "IC4") (pin "12") (pinfunction "VSS_12") (pintype "power_in"))
      (node (ref "IC5") (pin "12") (pinfunction "VSS_12") (pintype "power_in"))
      (node (ref "LED0") (pin "K") (pinfunction "C_K") (pintype "passive"))
      (node (ref "LED1") (pin "K") (pinfunction "C_K") (pintype "passive"))
      (node (ref "LED2") (pin "K") (pinfunction "C_K") (pintype "passive"))
      (node (ref "LED3") (pin "K") (pinfunction "C_K") (pintype "passive"))
      (node (ref "LED4") (pin "K") (pinfunction "C_K") (pintype "passive"))
      (node (ref "LED5") (pin "K") (pinfunction "C_K") (pintype "passive"))
      (node (ref "LED6") (pin "K") (pinfunction "C_K") (pintype "passive"))
      (node (ref "LED7") (pin "K") (pinfunction "C_K") (pintype "passive"))
      (node (ref "LED8") (pin "K") (pinfunction "C_K") (pintype "passive"))
      (node (ref "LED9") (pin "K") (pinfunction "C_K") (pintype "passive"))
      (node (ref "M0") (pin "1") (pinfunction "1_1") (pintype "bidirectional"))
      (node (ref "M1") (pin "1") (pinfunction "1_1") (pintype "bidirectional"))
      (node (ref "P0_0") (pin "1") (pinfunction "A_1") (pintype "passive"))
      (node (ref "P0_1") (pin "1") (pinfunction "A_1") (pintype "passive"))
      (node (ref "P0_2") (pin "1") (pinfunction "A_1") (pintype "passive"))
      (node (ref "P0_3") (pin "1") (pinfunction "A_1") (pintype "passive"))
      (node (ref "P0_4") (pin "1") (pinfunction "A_1") (pintype "passive"))
      (node (ref "P0_5") (pin "1") (pinfunction "A_1") (pintype "passive"))
      (node (ref "P0_6") (pin "1") (pinfunction "A_1") (pintype "passive"))
      (node (ref "P0_7") (pin "1") (pinfunction "A_1") (pintype "passive"))
      (node (ref "P0_8") (pin "1") (pinfunction "A_1") (pintype "passive"))
      (node (ref "P0_9") (pin "1") (pinfunction "A_1") (pintype "passive"))
      (node (ref "P1_0") (pin "1") (pinfunction "A_1") (pintype "passive"))
      (node (ref "P1_1") (pin "1") (pinfunction "A_1") (pintype "passive"))
      (node (ref "P1_2") (pin "1") (pinfunction "A_1") (pintype "passive"))
      (node (ref "P1_3") (pin "1") (pinfunction "A_1") (pintype "passive"))
      (node (ref "P1_4") (pin "1") (pinfunction "A_1") (pintype "passive"))
      (node (ref "P1_5") (pin "1") (pinfunction "A_1") (pintype "passive"))
      (node (ref "P1_6") (pin "1") (pinfunction "A_1") (pintype "passive"))
      (node (ref "P1_7") (pin "1") (pinfunction "A_1") (pintype "passive"))
      (node (ref "P1_8") (pin "1") (pinfunction "A_1") (pintype "passive"))
      (node (ref "P1_9") (pin "1") (pinfunction "A_1") (pintype "passive"))
      (node (ref "R1") (pin "1") (pinfunction "1_1") (pintype "passive"))
      (node (ref "R10") (pin "1") (pinfunction "1_1") (pintype "passive"))
      (node (ref "R2") (pin "1") (pinfunction "1_1") (pintype "passive"))
      (node (ref "R29") (pin "1") (pinfunction "1_1") (pintype "passive"))
      (node (ref "R3") (pin "1") (pinfunction "1_1") (pintype "passive"))
      (node (ref "R30") (pin "1") (pinfunction "1_1") (pintype "passive"))
      (node (ref "R31") (pin "1") (pinfunction "1_1") (pintype "passive"))
      (node (ref "R32") (pin "1") (pinfunction "1_1") (pintype "passive"))
      (node (ref "R33") (pin "1") (pinfunction "1_1") (pintype "passive"))
      (node (ref "R34") (pin "1") (pinfunction "1_1") (pintype "passive"))
      (node (ref "R35") (pin "1") (pinfunction "1_1") (pintype "passive"))
      (node (ref "R36") (pin "1") (pinfunction "1_1") (pintype "passive"))
      (node (ref "R37") (pin "1") (pinfunction "1_1") (pintype "passive"))
      (node (ref "R38") (pin "1") (pinfunction "1_1") (pintype "passive"))
      (node (ref "R4") (pin "1") (pinfunction "1_1") (pintype "passive"))
      (node (ref "R5") (pin "1") (pinfunction "1_1") (pintype "passive"))
      (node (ref "R6") (pin "1") (pinfunction "1_1") (pintype "passive"))
      (node (ref "R7") (pin "1") (pinfunction "1_1") (pintype "passive"))
      (node (ref "R8") (pin "1") (pinfunction "1_1") (pintype "passive"))
      (node (ref "R9") (pin "1") (pinfunction "1_1") (pintype "passive"))
      (node (ref "S0") (pin "1") (pinfunction "1_1") (pintype "bidirectional"))
      (node (ref "S1") (pin "1") (pinfunction "1_1") (pintype "bidirectional"))
      (node (ref "S2") (pin "1") (pinfunction "1_1") (pintype "bidirectional"))
      (node (ref "S3") (pin "1") (pinfunction "1_1") (pintype "bidirectional"))
      (node (ref "S4") (pin "1") (pinfunction "1_1") (pintype "bidirectional"))
      (node (ref "S5") (pin "1") (pinfunction "1_1") (pintype "bidirectional"))
      (node (ref "S6") (pin "1") (pinfunction "1_1") (pintype "bidirectional"))
      (node (ref "S7") (pin "1") (pinfunction "1_1") (pintype "bidirectional"))
      (node (ref "T1") (pin "E") (pinfunction "E_E") (pintype "passive"))
      (node (ref "T10") (pin "E") (pinfunction "E_E") (pintype "passive"))
      (node (ref "T2") (pin "E") (pinfunction "E_E") (pintype "passive"))
      (node (ref "T3") (pin "E") (pinfunction "E_E") (pintype "passive"))
      (node (ref "T4") (pin "E") (pinfunction "E_E") (pintype "passive"))
      (node (ref "T5") (pin "E") (pinfunction "E_E") (pintype "passive"))
      (node (ref "T6") (pin "E") (pinfunction "E_E") (pintype "passive"))
      (node (ref "T7") (pin "E") (pinfunction "E_E") (pintype "passive"))
      (node (ref "T8") (pin "E") (pinfunction "E_E") (pintype "passive"))
      (node (ref "T9") (pin "E") (pinfunction "E_E") (pintype "passive"))
      (node (ref "U$1") (pin "GND1") (pinfunction "GND1_GND1") (pintype "bidirectional"))
    )
    (net (code "17") (name "LED0") (class "Default")
      (node (ref "R40") (pin "2") (pinfunction "2_2") (pintype "passive"))
      (node (ref "U$1") (pin "0-RX1/CS1/CRX2") (pinfunction "0-RX1/CS1/CRX2_0-RX1/CS1/CRX2") (pintype "bidirectional"))
    )
    (net (code "18") (name "LED1") (class "Default")
      (node (ref "R39") (pin "2") (pinfunction "2_2") (pintype "passive"))
      (node (ref "U$1") (pin "1-TX1/MISO1/CTX2") (pinfunction "1-TX1/MISO1/CTX2_1-TX1/MISO1/CTX2") (pintype "bidirectional"))
    )
    (net (code "19") (name "LED2") (class "Default")
      (node (ref "R41") (pin "2") (pinfunction "2_2") (pintype "passive"))
      (node (ref "U$1") (pin "35-TX8") (pinfunction "35/TX8_35-TX8") (pintype "bidirectional"))
    )
    (net (code "20") (name "LED3") (class "Default")
      (node (ref "R42") (pin "2") (pinfunction "2_2") (pintype "passive"))
      (node (ref "U$1") (pin "11-MOSI/CTX1") (pinfunction "11-MOSI/CTX1_11-MOSI/CTX1") (pintype "bidirectional"))
    )
    (net (code "21") (name "LED4") (class "Default")
      (node (ref "R43") (pin "2") (pinfunction "2_2") (pintype "passive"))
      (node (ref "U$1") (pin "12-MISO/MQSL") (pinfunction "12-MISO/MQSL_12-MISO/MQSL") (pintype "bidirectional"))
    )
    (net (code "22") (name "LED5") (class "Default")
      (node (ref "R44") (pin "2") (pinfunction "2_2") (pintype "passive"))
      (node (ref "U$1") (pin "13-SCK/LED") (pinfunction "13-SCK/LED_13-SCK/LED") (pintype "bidirectional"))
    )
    (net (code "23") (name "LED6") (class "Default")
      (node (ref "R45") (pin "2") (pinfunction "2_2") (pintype "passive"))
      (node (ref "U$1") (pin "32-OUT1B") (pinfunction "32-OUT1B_32-OUT1B") (pintype "bidirectional"))
    )
    (net (code "24") (name "LED7") (class "Default")
      (node (ref "R46") (pin "2") (pinfunction "2_2") (pintype "passive"))
      (node (ref "U$1") (pin "33-MCLK2") (pinfunction "33-MCLK2_33-MCLK2") (pintype "bidirectional"))
    )
    (net (code "25") (name "LED8") (class "Default")
      (node (ref "R47") (pin "2") (pinfunction "2_2") (pintype "passive"))
      (node (ref "U$1") (pin "36-PWM") (pinfunction "36-PWM_36-PWM") (pintype "bidirectional"))
    )
    (net (code "26") (name "LED9") (class "Default")
      (node (ref "R48") (pin "2") (pinfunction "2_2") (pintype "passive"))
      (node (ref "U$1") (pin "37-PWM") (pinfunction "37-PWM_37-PWM") (pintype "bidirectional"))
    )
    (net (code "27") (name "Net-(IC1A-X0)") (class "Default")
      (node (ref "IC1") (pin "9") (pinfunction "X0_9") (pintype "input"))
      (node (ref "M1") (pin "2") (pinfunction "2_2") (pintype "bidirectional"))
    )
    (net (code "28") (name "Net-(IC1A-X1)") (class "Default")
      (node (ref "IC1") (pin "8") (pinfunction "X1_8") (pintype "input"))
      (node (ref "M0") (pin "2") (pinfunction "2_2") (pintype "bidirectional"))
    )
    (net (code "29") (name "Net-(IC1A-X2)") (class "Default")
      (node (ref "IC1") (pin "7") (pinfunction "X2_7") (pintype "input"))
      (node (ref "S7") (pin "2") (pinfunction "2_2") (pintype "bidirectional"))
    )
    (net (code "30") (name "Net-(IC1A-X3)") (class "Default")
      (node (ref "IC1") (pin "6") (pinfunction "X3_6") (pintype "input"))
      (node (ref "S6") (pin "2") (pinfunction "2_2") (pintype "bidirectional"))
    )
    (net (code "31") (name "Net-(IC1A-X4)") (class "Default")
      (node (ref "IC1") (pin "5") (pinfunction "X4_5") (pintype "input"))
      (node (ref "S5") (pin "2") (pinfunction "2_2") (pintype "bidirectional"))
    )
    (net (code "32") (name "Net-(IC1A-X5)") (class "Default")
      (node (ref "IC1") (pin "4") (pinfunction "X5_4") (pintype "input"))
      (node (ref "S4") (pin "2") (pinfunction "2_2") (pintype "bidirectional"))
    )
    (net (code "33") (name "Net-(IC1A-X6)") (class "Default")
      (node (ref "IC1") (pin "3") (pinfunction "X6_3") (pintype "input"))
      (node (ref "S3") (pin "2") (pinfunction "2_2") (pintype "bidirectional"))
    )
    (net (code "34") (name "Net-(IC1A-X7)") (class "Default")
      (node (ref "IC1") (pin "2") (pinfunction "X7_2") (pintype "input"))
      (node (ref "S2") (pin "2") (pinfunction "2_2") (pintype "bidirectional"))
    )
    (net (code "35") (name "Net-(IC1A-X8)") (class "Default")
      (node (ref "IC1") (pin "23") (pinfunction "X8_23") (pintype "input"))
      (node (ref "S1") (pin "2") (pinfunction "2_2") (pintype "bidirectional"))
    )
    (net (code "36") (name "Net-(IC1A-X9)") (class "Default")
      (node (ref "IC1") (pin "22") (pinfunction "X9_22") (pintype "input"))
      (node (ref "S0") (pin "2") (pinfunction "2_2") (pintype "bidirectional"))
    )
    (net (code "37") (name "Net-(IC2A-X0)") (class "Default")
      (node (ref "IC2") (pin "9") (pinfunction "X0_9") (pintype "input"))
      (node (ref "SW9") (pin "4") (pinfunction "P1_4") (pintype "passive"))
    )
    (net (code "38") (name "Net-(IC2A-X1)") (class "Default")
      (node (ref "IC2") (pin "8") (pinfunction "X1_8") (pintype "input"))
      (node (ref "SW8") (pin "4") (pinfunction "P1_4") (pintype "passive"))
    )
    (net (code "39") (name "Net-(IC2A-X2)") (class "Default")
      (node (ref "IC2") (pin "7") (pinfunction "X2_7") (pintype "input"))
      (node (ref "SW7") (pin "4") (pinfunction "P1_4") (pintype "passive"))
    )
    (net (code "40") (name "Net-(IC2A-X3)") (class "Default")
      (node (ref "IC2") (pin "6") (pinfunction "X3_6") (pintype "input"))
      (node (ref "SW6") (pin "4") (pinfunction "P1_4") (pintype "passive"))
    )
    (net (code "41") (name "Net-(IC2A-X4)") (class "Default")
      (node (ref "IC2") (pin "5") (pinfunction "X4_5") (pintype "input"))
      (node (ref "SW5") (pin "4") (pinfunction "P1_4") (pintype "passive"))
    )
    (net (code "42") (name "Net-(IC2A-X5)") (class "Default")
      (node (ref "IC2") (pin "4") (pinfunction "X5_4") (pintype "input"))
      (node (ref "SW4") (pin "4") (pinfunction "P1_4") (pintype "passive"))
    )
    (net (code "43") (name "Net-(IC2A-X6)") (class "Default")
      (node (ref "IC2") (pin "3") (pinfunction "X6_3") (pintype "input"))
      (node (ref "SW3") (pin "4") (pinfunction "P1_4") (pintype "passive"))
    )
    (net (code "44") (name "Net-(IC2A-X7)") (class "Default")
      (node (ref "IC2") (pin "2") (pinfunction "X7_2") (pintype "input"))
      (node (ref "SW2") (pin "4") (pinfunction "P1_4") (pintype "passive"))
    )
    (net (code "45") (name "Net-(IC2A-X8)") (class "Default")
      (node (ref "IC2") (pin "23") (pinfunction "X8_23") (pintype "input"))
      (node (ref "SW1") (pin "4") (pinfunction "P1_4") (pintype "passive"))
    )
    (net (code "46") (name "Net-(IC2A-X9)") (class "Default")
      (node (ref "IC2") (pin "22") (pinfunction "X9_22") (pintype "input"))
      (node (ref "SW0") (pin "4") (pinfunction "P1_4") (pintype "passive"))
    )
    (net (code "47") (name "Net-(IC3A-X0)") (class "Default")
      (node (ref "IC3") (pin "9") (pinfunction "X0_9") (pintype "input"))
      (node (ref "P0_9") (pin "2") (pinfunction "S_2") (pintype "passive"))
    )
    (net (code "48") (name "Net-(IC3A-X1)") (class "Default")
      (node (ref "IC3") (pin "8") (pinfunction "X1_8") (pintype "input"))
      (node (ref "P0_8") (pin "2") (pinfunction "S_2") (pintype "passive"))
    )
    (net (code "49") (name "Net-(IC3A-X2)") (class "Default")
      (node (ref "IC3") (pin "7") (pinfunction "X2_7") (pintype "input"))
      (node (ref "P0_7") (pin "2") (pinfunction "S_2") (pintype "passive"))
    )
    (net (code "50") (name "Net-(IC3A-X3)") (class "Default")
      (node (ref "IC3") (pin "6") (pinfunction "X3_6") (pintype "input"))
      (node (ref "P0_6") (pin "2") (pinfunction "S_2") (pintype "passive"))
    )
    (net (code "51") (name "Net-(IC3A-X4)") (class "Default")
      (node (ref "IC3") (pin "5") (pinfunction "X4_5") (pintype "input"))
      (node (ref "P0_5") (pin "2") (pinfunction "S_2") (pintype "passive"))
    )
    (net (code "52") (name "Net-(IC3A-X5)") (class "Default")
      (node (ref "IC3") (pin "4") (pinfunction "X5_4") (pintype "input"))
      (node (ref "P0_4") (pin "2") (pinfunction "S_2") (pintype "passive"))
    )
    (net (code "53") (name "Net-(IC3A-X6)") (class "Default")
      (node (ref "IC3") (pin "3") (pinfunction "X6_3") (pintype "input"))
      (node (ref "P0_3") (pin "2") (pinfunction "S_2") (pintype "passive"))
    )
    (net (code "54") (name "Net-(IC3A-X7)") (class "Default")
      (node (ref "IC3") (pin "2") (pinfunction "X7_2") (pintype "input"))
      (node (ref "P0_2") (pin "2") (pinfunction "S_2") (pintype "passive"))
    )
    (net (code "55") (name "Net-(IC3A-X8)") (class "Default")
      (node (ref "IC3") (pin "23") (pinfunction "X8_23") (pintype "input"))
      (node (ref "P0_1") (pin "2") (pinfunction "S_2") (pintype "passive"))
    )
    (net (code "56") (name "Net-(IC3A-X9)") (class "Default")
      (node (ref "IC3") (pin "22") (pinfunction "X9_22") (pintype "input"))
      (node (ref "P0_0") (pin "2") (pinfunction "S_2") (pintype "passive"))
    )
    (net (code "57") (name "Net-(IC4A-X0)") (class "Default")
      (node (ref "IC4") (pin "9") (pinfunction "X0_9") (pintype "input"))
      (node (ref "P1_9") (pin "2") (pinfunction "S_2") (pintype "passive"))
    )
    (net (code "58") (name "Net-(IC4A-X1)") (class "Default")
      (node (ref "IC4") (pin "8") (pinfunction "X1_8") (pintype "input"))
      (node (ref "P1_8") (pin "2") (pinfunction "S_2") (pintype "passive"))
    )
    (net (code "59") (name "Net-(IC4A-X2)") (class "Default")
      (node (ref "IC4") (pin "7") (pinfunction "X2_7") (pintype "input"))
      (node (ref "P1_7") (pin "2") (pinfunction "S_2") (pintype "passive"))
    )
    (net (code "60") (name "Net-(IC4A-X3)") (class "Default")
      (node (ref "IC4") (pin "6") (pinfunction "X3_6") (pintype "input"))
      (node (ref "P1_6") (pin "2") (pinfunction "S_2") (pintype "passive"))
    )
    (net (code "61") (name "Net-(IC4A-X4)") (class "Default")
      (node (ref "IC4") (pin "5") (pinfunction "X4_5") (pintype "input"))
      (node (ref "P1_5") (pin "2") (pinfunction "S_2") (pintype "passive"))
    )
    (net (code "62") (name "Net-(IC4A-X5)") (class "Default")
      (node (ref "IC4") (pin "4") (pinfunction "X5_4") (pintype "input"))
      (node (ref "P1_4") (pin "2") (pinfunction "S_2") (pintype "passive"))
    )
    (net (code "63") (name "Net-(IC4A-X6)") (class "Default")
      (node (ref "IC4") (pin "3") (pinfunction "X6_3") (pintype "input"))
      (node (ref "P1_3") (pin "2") (pinfunction "S_2") (pintype "passive"))
    )
    (net (code "64") (name "Net-(IC4A-X7)") (class "Default")
      (node (ref "IC4") (pin "2") (pinfunction "X7_2") (pintype "input"))
      (node (ref "P1_2") (pin "2") (pinfunction "S_2") (pintype "passive"))
    )
    (net (code "65") (name "Net-(IC4A-X8)") (class "Default")
      (node (ref "IC4") (pin "23") (pinfunction "X8_23") (pintype "input"))
      (node (ref "P1_1") (pin "2") (pinfunction "S_2") (pintype "passive"))
    )
    (net (code "66") (name "Net-(IC4A-X9)") (class "Default")
      (node (ref "IC4") (pin "22") (pinfunction "X9_22") (pintype "input"))
      (node (ref "P1_0") (pin "2") (pinfunction "S_2") (pintype "passive"))
    )
    (net (code "67") (name "Net-(IC5A-X0)") (class "Default")
      (node (ref "IC5") (pin "9") (pinfunction "X0_9") (pintype "input"))
      (node (ref "MS9") (pin "4") (pinfunction "P1_4") (pintype "passive"))
    )
    (net (code "68") (name "Net-(IC5A-X1)") (class "Default")
      (node (ref "IC5") (pin "8") (pinfunction "X1_8") (pintype "input"))
      (node (ref "MS8") (pin "4") (pinfunction "P1_4") (pintype "passive"))
    )
    (net (code "69") (name "Net-(IC5A-X2)") (class "Default")
      (node (ref "IC5") (pin "7") (pinfunction "X2_7") (pintype "input"))
      (node (ref "MS7") (pin "4") (pinfunction "P1_4") (pintype "passive"))
    )
    (net (code "70") (name "Net-(IC5A-X3)") (class "Default")
      (node (ref "IC5") (pin "6") (pinfunction "X3_6") (pintype "input"))
      (node (ref "MS6") (pin "4") (pinfunction "P1_4") (pintype "passive"))
    )
    (net (code "71") (name "Net-(IC5A-X4)") (class "Default")
      (node (ref "IC5") (pin "5") (pinfunction "X4_5") (pintype "input"))
      (node (ref "MS5") (pin "4") (pinfunction "P1_4") (pintype "passive"))
    )
    (net (code "72") (name "Net-(IC5A-X5)") (class "Default")
      (node (ref "IC5") (pin "4") (pinfunction "X5_4") (pintype "input"))
      (node (ref "MS4") (pin "4") (pinfunction "P1_4") (pintype "passive"))
    )
    (net (code "73") (name "Net-(IC5A-X6)") (class "Default")
      (node (ref "IC5") (pin "3") (pinfunction "X6_3") (pintype "input"))
      (node (ref "MS3") (pin "4") (pinfunction "P1_4") (pintype "passive"))
    )
    (net (code "74") (name "Net-(IC5A-X7)") (class "Default")
      (node (ref "IC5") (pin "2") (pinfunction "X7_2") (pintype "input"))
      (node (ref "MS2") (pin "4") (pinfunction "P1_4") (pintype "passive"))
    )
    (net (code "75") (name "Net-(IC5A-X8)") (class "Default")
      (node (ref "IC5") (pin "23") (pinfunction "X8_23") (pintype "input"))
      (node (ref "MS1") (pin "4") (pinfunction "P1_4") (pintype "passive"))
    )
    (net (code "76") (name "Net-(IC5A-X9)") (class "Default")
      (node (ref "IC5") (pin "22") (pinfunction "X9_22") (pintype "input"))
      (node (ref "MS0") (pin "4") (pinfunction "P1_4") (pintype "passive"))
    )
    (net (code "77") (name "Net-(LED0-PadA)") (class "Default")
      (node (ref "LED0") (pin "A") (pinfunction "A_A") (pintype "passive"))
      (node (ref "R40") (pin "1") (pinfunction "1_1") (pintype "passive"))
    )
    (net (code "78") (name "Net-(LED1-PadA)") (class "Default")
      (node (ref "LED1") (pin "A") (pinfunction "A_A") (pintype "passive"))
      (node (ref "R39") (pin "1") (pinfunction "1_1") (pintype "passive"))
    )
    (net (code "79") (name "Net-(LED2-PadA)") (class "Default")
      (node (ref "LED2") (pin "A") (pinfunction "A_A") (pintype "passive"))
      (node (ref "R41") (pin "1") (pinfunction "1_1") (pintype "passive"))
    )
    (net (code "80") (name "Net-(LED3-PadA)") (class "Default")
      (node (ref "LED3") (pin "A") (pinfunction "A_A") (pintype "passive"))
      (node (ref "R42") (pin "1") (pinfunction "1_1") (pintype "passive"))
    )
    (net (code "81") (name "Net-(LED4-PadA)") (class "Default")
      (node (ref "LED4") (pin "A") (pinfunction "A_A") (pintype "passive"))
      (node (ref "R43") (pin "1") (pinfunction "1_1") (pintype "passive"))
    )
    (net (code "82") (name "Net-(LED5-PadA)") (class "Default")
      (node (ref "LED5") (pin "A") (pinfunction "A_A") (pintype "passive"))
      (node (ref "R44") (pin "1") (pinfunction "1_1") (pintype "passive"))
    )
    (net (code "83") (name "Net-(LED6-PadA)") (class "Default")
      (node (ref "LED6") (pin "A") (pinfunction "A_A") (pintype "passive"))
      (node (ref "R45") (pin "1") (pinfunction "1_1") (pintype "passive"))
    )
    (net (code "84") (name "Net-(LED7-PadA)") (class "Default")
      (node (ref "LED7") (pin "A") (pinfunction "A_A") (pintype "passive"))
      (node (ref "R46") (pin "1") (pinfunction "1_1") (pintype "passive"))
    )
    (net (code "85") (name "Net-(LED8-PadA)") (class "Default")
      (node (ref "LED8") (pin "A") (pinfunction "A_A") (pintype "passive"))
      (node (ref "R47") (pin "1") (pinfunction "1_1") (pintype "passive"))
    )
    (net (code "86") (name "Net-(LED9-PadA)") (class "Default")
      (node (ref "LED9") (pin "A") (pinfunction "A_A") (pintype "passive"))
      (node (ref "R48") (pin "1") (pinfunction "1_1") (pintype "passive"))
    )
    (net (code "87") (name "Net-(MS0-P)") (class "Default")
      (node (ref "MS0") (pin "3") (pinfunction "P_3") (pintype "passive"))
      (node (ref "R29") (pin "2") (pinfunction "2_2") (pintype "passive"))
    )
    (net (code "88") (name "Net-(MS1-P)") (class "Default")
      (node (ref "MS1") (pin "3") (pinfunction "P_3") (pintype "passive"))
      (node (ref "R30") (pin "2") (pinfunction "2_2") (pintype "passive"))
    )
    (net (code "89") (name "Net-(MS2-P)") (class "Default")
      (node (ref "MS2") (pin "3") (pinfunction "P_3") (pintype "passive"))
      (node (ref "R31") (pin "2") (pinfunction "2_2") (pintype "passive"))
    )
    (net (code "90") (name "Net-(MS3-P)") (class "Default")
      (node (ref "MS3") (pin "3") (pinfunction "P_3") (pintype "passive"))
      (node (ref "R32") (pin "2") (pinfunction "2_2") (pintype "passive"))
    )
    (net (code "91") (name "Net-(MS4-P)") (class "Default")
      (node (ref "MS4") (pin "3") (pinfunction "P_3") (pintype "passive"))
      (node (ref "R38") (pin "2") (pinfunction "2_2") (pintype "passive"))
    )
    (net (code "92") (name "Net-(MS5-P)") (class "Default")
      (node (ref "MS5") (pin "3") (pinfunction "P_3") (pintype "passive"))
      (node (ref "R33") (pin "2") (pinfunction "2_2") (pintype "passive"))
    )
    (net (code "93") (name "Net-(MS6-P)") (class "Default")
      (node (ref "MS6") (pin "3") (pinfunction "P_3") (pintype "passive"))
      (node (ref "R34") (pin "2") (pinfunction "2_2") (pintype "passive"))
    )
    (net (code "94") (name "Net-(MS7-P)") (class "Default")
      (node (ref "MS7") (pin "3") (pinfunction "P_3") (pintype "passive"))
      (node (ref "R35") (pin "2") (pinfunction "2_2") (pintype "passive"))
    )
    (net (code "95") (name "Net-(MS8-P)") (class "Default")
      (node (ref "MS8") (pin "3") (pinfunction "P_3") (pintype "passive"))
      (node (ref "R36") (pin "2") (pinfunction "2_2") (pintype "passive"))
    )
    (net (code "96") (name "Net-(MS9-P)") (class "Default")
      (node (ref "MS9") (pin "3") (pinfunction "P_3") (pintype "passive"))
      (node (ref "R37") (pin "2") (pinfunction "2_2") (pintype "passive"))
    )
    (net (code "97") (name "Net-(R11-Pad2)") (class "Default")
      (node (ref "R11") (pin "2") (pinfunction "2_2") (pintype "passive"))
      (node (ref "T1") (pin "B") (pinfunction "B_B") (pintype "passive"))
    )
    (net (code "98") (name "Net-(R12-Pad2)") (class "Default")
      (node (ref "R12") (pin "2") (pinfunction "2_2") (pintype "passive"))
      (node (ref "T2") (pin "B") (pinfunction "B_B") (pintype "passive"))
    )
    (net (code "99") (name "Net-(R13-Pad2)") (class "Default")
      (node (ref "R13") (pin "2") (pinfunction "2_2") (pintype "passive"))
      (node (ref "T3") (pin "B") (pinfunction "B_B") (pintype "passive"))
    )
    (net (code "100") (name "Net-(R14-Pad2)") (class "Default")
      (node (ref "R14") (pin "2") (pinfunction "2_2") (pintype "passive"))
      (node (ref "T4") (pin "B") (pinfunction "B_B") (pintype "passive"))
    )
    (net (code "101") (name "Net-(R15-Pad2)") (class "Default")
      (node (ref "R15") (pin "2") (pinfunction "2_2") (pintype "passive"))
      (node (ref "T5") (pin "B") (pinfunction "B_B") (pintype "passive"))
    )
    (net (code "102") (name "Net-(R24-Pad2)") (class "Default")
      (node (ref "R24") (pin "2") (pinfunction "2_2") (pintype "passive"))
      (node (ref "T6") (pin "B") (pinfunction "B_B") (pintype "passive"))
    )
    (net (code "103") (name "Net-(R25-Pad2)") (class "Default")
      (node (ref "R25") (pin "2") (pinfunction "2_2") (pintype "passive"))
      (node (ref "T7") (pin "B") (pinfunction "B_B") (pintype "passive"))
    )
    (net (code "104") (name "Net-(R26-Pad2)") (class "Default")
      (node (ref "R26") (pin "2") (pinfunction "2_2") (pintype "passive"))
      (node (ref "T8") (pin "B") (pinfunction "B_B") (pintype "passive"))
    )
    (net (code "105") (name "Net-(R27-Pad2)") (class "Default")
      (node (ref "R27") (pin "2") (pinfunction "2_2") (pintype "passive"))
      (node (ref "T9") (pin "B") (pinfunction "B_B") (pintype "passive"))
    )
    (net (code "106") (name "Net-(R28-Pad2)") (class "Default")
      (node (ref "R28") (pin "2") (pinfunction "2_2") (pintype "passive"))
      (node (ref "T10") (pin "B") (pinfunction "B_B") (pintype "passive"))
    )
    (net (code "107") (name "Net-(SW0-P)") (class "Default")
      (node (ref "R1") (pin "2") (pinfunction "2_2") (pintype "passive"))
      (node (ref "SW0") (pin "3") (pinfunction "P_3") (pintype "passive"))
    )
    (net (code "108") (name "Net-(SW1-P)") (class "Default")
      (node (ref "R2") (pin "2") (pinfunction "2_2") (pintype "passive"))
      (node (ref "SW1") (pin "3") (pinfunction "P_3") (pintype "passive"))
    )
    (net (code "109") (name "Net-(SW2-P)") (class "Default")
      (node (ref "R3") (pin "2") (pinfunction "2_2") (pintype "passive"))
      (node (ref "SW2") (pin "3") (pinfunction "P_3") (pintype "passive"))
    )
    (net (code "110") (name "Net-(SW3-P)") (class "Default")
      (node (ref "R4") (pin "2") (pinfunction "2_2") (pintype "passive"))
      (node (ref "SW3") (pin "3") (pinfunction "P_3") (pintype "passive"))
    )
    (net (code "111") (name "Net-(SW4-P)") (class "Default")
      (node (ref "R10") (pin "2") (pinfunction "2_2") (pintype "passive"))
      (node (ref "SW4") (pin "3") (pinfunction "P_3") (pintype "passive"))
    )
    (net (code "112") (name "Net-(SW5-P)") (class "Default")
      (node (ref "R5") (pin "2") (pinfunction "2_2") (pintype "passive"))
      (node (ref "SW5") (pin "3") (pinfunction "P_3") (pintype "passive"))
    )
    (net (code "113") (name "Net-(SW6-P)") (class "Default")
      (node (ref "R6") (pin "2") (pinfunction "2_2") (pintype "passive"))
      (node (ref "SW6") (pin "3") (pinfunction "P_3") (pintype "passive"))
    )
    (net (code "114") (name "Net-(SW7-P)") (class "Default")
      (node (ref "R7") (pin "2") (pinfunction "2_2") (pintype "passive"))
      (node (ref "SW7") (pin "3") (pinfunction "P_3") (pintype "passive"))
    )
    (net (code "115") (name "Net-(SW8-P)") (class "Default")
      (node (ref "R8") (pin "2") (pinfunction "2_2") (pintype "passive"))
      (node (ref "SW8") (pin "3") (pinfunction "P_3") (pintype "passive"))
    )
    (net (code "116") (name "Net-(SW9-P)") (class "Default")
      (node (ref "R9") (pin "2") (pinfunction "2_2") (pintype "passive"))
      (node (ref "SW9") (pin "3") (pinfunction "P_3") (pintype "passive"))
    )
    (net (code "117") (name "POT0_INH") (class "Default")
      (node (ref "IC3") (pin "15") (pinfunction "INH_15") (pintype "input"))
      (node (ref "U$1") (pin "8-TX2/IN1") (pinfunction "8-TX2/IN1_8-TX2/IN1") (pintype "bidirectional"))
    )
    (net (code "118") (name "POT0_X") (class "Default")
      (node (ref "IC3") (pin "1") (pinfunction "X_1") (pintype "output"))
      (node (ref "U$1") (pin "16-A2/RX4/SCL1") (pinfunction "16-A2/RX4/SCL1_16-A2/RX4/SCL1") (pintype "bidirectional"))
    )
    (net (code "119") (name "POT1_INH") (class "Default")
      (node (ref "IC4") (pin "15") (pinfunction "INH_15") (pintype "input"))
      (node (ref "U$1") (pin "9-OUT1C") (pinfunction "9-OUT1C_9-OUT1C") (pintype "bidirectional"))
    )
    (net (code "120") (name "POT1_X") (class "Default")
      (node (ref "IC4") (pin "1") (pinfunction "X_1") (pintype "output"))
      (node (ref "U$1") (pin "17-A3/TX4/SDA1") (pinfunction "17-A3/TX4/SDA1_17-A3/TX4/SDA1") (pintype "bidirectional"))
    )
    (net (code "121") (name "SEG_A") (class "Default")
      (node (ref "R16") (pin "1") (pinfunction "1_1") (pintype "passive"))
      (node (ref "U$1") (pin "39-A15/CS/OUT1A") (pinfunction "39-A15/CS/OUT1A_39-A15/CS/OUT1A") (pintype "bidirectional"))
    )
    (net (code "122") (name "SEG_B") (class "Default")
      (node (ref "R17") (pin "1") (pinfunction "1_1") (pintype "passive"))
      (node (ref "U$1") (pin "40-A16/CS1") (pinfunction "40-A16/CS1_40-A16/CS1") (pintype "bidirectional"))
    )
    (net (code "123") (name "SEG_C") (class "Default")
      (node (ref "R18") (pin "1") (pinfunction "1_1") (pintype "passive"))
      (node (ref "U$1") (pin "41-A17/MISO1") (pinfunction "41-A17/MISO1_41-A17/MISO1") (pintype "bidirectional"))
    )
    (net (code "124") (name "SEG_D") (class "Default")
      (node (ref "R19") (pin "1") (pinfunction "1_1") (pintype "passive"))
      (node (ref "U$1") (pin "30-CRX3") (pinfunction "30-CRX3_30-CRX3") (pintype "bidirectional"))
    )
    (net (code "125") (name "SEG_E") (class "Default")
      (node (ref "R20") (pin "1") (pinfunction "1_1") (pintype "passive"))
      (node (ref "U$1") (pin "31-CTX3") (pinfunction "31-CTX3_31-CTX3") (pintype "bidirectional"))
    )
    (net (code "126") (name "SEG_F") (class "Default")
      (node (ref "R21") (pin "1") (pinfunction "1_1") (pintype "passive"))
      (node (ref "U$1") (pin "28-RX7") (pinfunction "28-RX7_28-RX7") (pintype "bidirectional"))
    )
    (net (code "127") (name "SEG_G") (class "Default")
      (node (ref "R22") (pin "1") (pinfunction "1_1") (pintype "passive"))
      (node (ref "U$1") (pin "29-TX7") (pinfunction "29-TX7_29-TX7") (pintype "bidirectional"))
    )
    (net (code "128") (name "SEG_K0") (class "Default")
      (node (ref "R11") (pin "1") (pinfunction "1_1") (pintype "passive"))
      (node (ref "U$1") (pin "19-A5/SCL0") (pinfunction "19-A5/SCL0_19-A5/SCL0") (pintype "bidirectional"))
    )
    (net (code "129") (name "SEG_K1") (class "Default")
      (node (ref "R12") (pin "1") (pinfunction "1_1") (pintype "passive"))
      (node (ref "U$1") (pin "20-A6/TX5/LRCLK1") (pinfunction "20-A6/TX5/LRCLK1_20-A6/TX5/LRCLK1") (pintype "bidirectional"))
    )
    (net (code "130") (name "SEG_K1AA") (class "Default")
      (node (ref "D1") (pin "3") (pinfunction "CK1_3") (pintype "passive"))
      (node (ref "D1") (pin "8") (pinfunction "CK2_8") (pintype "passive"))
      (node (ref "T2") (pin "C") (pinfunction "C_C") (pintype "passive"))
    )
    (net (code "131") (name "SEG_K1AAAAV") (class "Default")
      (node (ref "D6") (pin "3") (pinfunction "CK1_3") (pintype "passive"))
      (node (ref "D6") (pin "8") (pinfunction "CK2_8") (pintype "passive"))
      (node (ref "T7") (pin "C") (pinfunction "C_C") (pintype "passive"))
    )
    (net (code "132") (name "SEG_K2") (class "Default")
      (node (ref "R13") (pin "1") (pinfunction "1_1") (pintype "passive"))
      (node (ref "U$1") (pin "21-A7/RX5/BCLK1") (pinfunction "21-A7/RX5/BCLK1_21-A7/RX5/BCLK1") (pintype "bidirectional"))
    )
    (net (code "133") (name "SEG_K2AA") (class "Default")
      (node (ref "D2") (pin "3") (pinfunction "CK1_3") (pintype "passive"))
      (node (ref "D2") (pin "8") (pinfunction "CK2_8") (pintype "passive"))
      (node (ref "T3") (pin "C") (pinfunction "C_C") (pintype "passive"))
    )
    (net (code "134") (name "SEG_K2VVV") (class "Default")
      (node (ref "D7") (pin "3") (pinfunction "CK1_3") (pintype "passive"))
      (node (ref "D7") (pin "8") (pinfunction "CK2_8") (pintype "passive"))
      (node (ref "T8") (pin "C") (pinfunction "C_C") (pintype "passive"))
    )
    (net (code "135") (name "SEG_K3") (class "Default")
      (node (ref "R14") (pin "1") (pinfunction "1_1") (pintype "passive"))
      (node (ref "U$1") (pin "22-A8/CTX1") (pinfunction "22-A8/CTX1_22-A8/CTX1") (pintype "bidirectional"))
    )
    (net (code "136") (name "SEG_K3AA") (class "Default")
      (node (ref "D3") (pin "3") (pinfunction "CK1_3") (pintype "passive"))
      (node (ref "D3") (pin "8") (pinfunction "CK2_8") (pintype "passive"))
      (node (ref "T4") (pin "C") (pinfunction "C_C") (pintype "passive"))
    )
    (net (code "137") (name "SEG_K3VVV") (class "Default")
      (node (ref "D8") (pin "3") (pinfunction "CK1_3") (pintype "passive"))
      (node (ref "D8") (pin "8") (pinfunction "CK2_8") (pintype "passive"))
      (node (ref "T9") (pin "C") (pinfunction "C_C") (pintype "passive"))
    )
    (net (code "138") (name "SEG_K4") (class "Default")
      (node (ref "R15") (pin "1") (pinfunction "1_1") (pintype "passive"))
      (node (ref "U$1") (pin "23-A9/CRX1/MCLK1") (pinfunction "23-A9/CRX1/MCLK1_23-A9/CRX1/MCLK1") (pintype "bidirectional"))
    )
    (net (code "139") (name "SEG_K4AA") (class "Default")
      (node (ref "D4") (pin "3") (pinfunction "CK1_3") (pintype "passive"))
      (node (ref "D4") (pin "8") (pinfunction "CK2_8") (pintype "passive"))
      (node (ref "T5") (pin "C") (pinfunction "C_C") (pintype "passive"))
    )
    (net (code "140") (name "SEG_K4VDF") (class "Default")
      (node (ref "D9") (pin "3") (pinfunction "CK1_3") (pintype "passive"))
      (node (ref "D9") (pin "8") (pinfunction "CK2_8") (pintype "passive"))
      (node (ref "T10") (pin "C") (pinfunction "C_C") (pintype "passive"))
    )
    (net (code "141") (name "SEG_K5") (class "Default")
      (node (ref "R24") (pin "1") (pinfunction "1_1") (pintype "passive"))
      (node (ref "U$1") (pin "24-A10/TX6/SCL2") (pinfunction "24-A10/TX6/SCL2_24-A10/TX6/SCL2") (pintype "bidirectional"))
    )
    (net (code "142") (name "SEG_K6") (class "Default")
      (node (ref "R25") (pin "1") (pinfunction "1_1") (pintype "passive"))
      (node (ref "U$1") (pin "25-A11/RX6/SDA2") (pinfunction "25-A11/RX6/SDA2_25-A11/RX6/SDA2") (pintype "bidirectional"))
    )
    (net (code "143") (name "SEG_K7") (class "Default")
      (node (ref "R26") (pin "1") (pinfunction "1_1") (pintype "passive"))
      (node (ref "U$1") (pin "26-A12/MOSI1") (pinfunction "26-A12/MOSI1_26-A12/MOSI1") (pintype "bidirectional"))
    )
    (net (code "144") (name "SEG_K8") (class "Default")
      (node (ref "R27") (pin "1") (pinfunction "1_1") (pintype "passive"))
      (node (ref "U$1") (pin "27-A13/SCK1") (pinfunction "27-A13/SCK1_27-A13/SCK1") (pintype "bidirectional"))
    )
    (net (code "145") (name "SEG_K9") (class "Default")
      (node (ref "R28") (pin "1") (pinfunction "1_1") (pintype "passive"))
      (node (ref "U$1") (pin "38-A14/CS/IN1") (pinfunction "38-A14/CS/IN1_38-A14/CS/IN1") (pintype "bidirectional"))
    )
    (net (code "146") (name "SEG_P") (class "Default")
      (node (ref "R23") (pin "1") (pinfunction "1_1") (pintype "passive"))
      (node (ref "U$1") (pin "34-RX8") (pinfunction "34-RX8_34-RX8") (pintype "bidirectional"))
    )
    (net (code "147") (name "SIG_K0AA") (class "Default")
      (node (ref "D0") (pin "3") (pinfunction "CK1_3") (pintype "passive"))
      (node (ref "D0") (pin "8") (pinfunction "CK2_8") (pintype "passive"))
      (node (ref "T1") (pin "C") (pinfunction "C_C") (pintype "passive"))
    )
    (net (code "148") (name "SIG_K1AA") (class "Default")
      (node (ref "D5") (pin "3") (pinfunction "CK1_3") (pintype "passive"))
      (node (ref "D5") (pin "8") (pinfunction "CK2_8") (pintype "passive"))
      (node (ref "T6") (pin "C") (pinfunction "C_C") (pintype "passive"))
    )
    (net (code "149") (name "SWITCH2_INH") (class "Default")
      (node (ref "IC5") (pin "15") (pinfunction "INH_15") (pintype "input"))
      (node (ref "U$1") (pin "10-CS\\MQSR") (pinfunction "10-CS/MQSR_10-CS\\MQSR") (pintype "bidirectional"))
    )
    (net (code "150") (name "SWITCH2_X") (class "Default")
      (node (ref "IC5") (pin "1") (pinfunction "X_1") (pintype "output"))
      (node (ref "U$1") (pin "18-A4/SDA0") (pinfunction "18-A4/SDA0_18-A4/SDA0") (pintype "bidirectional"))
    )
    (net (code "151") (name "SWITCH_INH") (class "Default")
      (node (ref "IC2") (pin "15") (pinfunction "INH_15") (pintype "input"))
      (node (ref "U$1") (pin "7-RX2/OUT1A") (pinfunction "7-RX2/OUT1A_7-RX2/OUT1A") (pintype "bidirectional"))
    )
    (net (code "152") (name "SWITCH_X") (class "Default")
      (node (ref "IC2") (pin "1") (pinfunction "X_1") (pintype "output"))
      (node (ref "U$1") (pin "15-A1/RX3/SPDIF_IN") (pinfunction "15-A1/RX3/SPDIF_IN_15-A1/RX3/SPDIF_IN") (pintype "bidirectional"))
    )
    (net (code "153") (name "unconnected-(IC1A-X10-Pad21)") (class "Default")
      (node (ref "IC1") (pin "21") (pinfunction "X10_21") (pintype "input"))
    )
    (net (code "154") (name "unconnected-(IC1A-X11-Pad20)") (class "Default")
      (node (ref "IC1") (pin "20") (pinfunction "X11_20") (pintype "input"))
    )
    (net (code "155") (name "unconnected-(IC1A-X12-Pad19)") (class "Default")
      (node (ref "IC1") (pin "19") (pinfunction "X12_19") (pintype "input"))
    )
    (net (code "156") (name "unconnected-(IC1A-X13-Pad18)") (class "Default")
      (node (ref "IC1") (pin "18") (pinfunction "X13_18") (pintype "input"))
    )
    (net (code "157") (name "unconnected-(IC1A-X14-Pad17)") (class "Default")
      (node (ref "IC1") (pin "17") (pinfunction "X14_17") (pintype "input"))
    )
    (net (code "158") (name "unconnected-(IC1A-X15-Pad16)") (class "Default")
      (node (ref "IC1") (pin "16") (pinfunction "X15_16") (pintype "input"))
    )
    (net (code "159") (name "unconnected-(IC2A-X10-Pad21)") (class "Default")
      (node (ref "IC2") (pin "21") (pinfunction "X10_21") (pintype "input"))
    )
    (net (code "160") (name "unconnected-(IC2A-X11-Pad20)") (class "Default")
      (node (ref "IC2") (pin "20") (pinfunction "X11_20") (pintype "input"))
    )
    (net (code "161") (name "unconnected-(IC2A-X12-Pad19)") (class "Default")
      (node (ref "IC2") (pin "19") (pinfunction "X12_19") (pintype "input"))
    )
    (net (code "162") (name "unconnected-(IC2A-X13-Pad18)") (class "Default")
      (node (ref "IC2") (pin "18") (pinfunction "X13_18") (pintype "input"))
    )
    (net (code "163") (name "unconnected-(IC2A-X14-Pad17)") (class "Default")
      (node (ref "IC2") (pin "17") (pinfunction "X14_17") (pintype "input"))
    )
    (net (code "164") (name "unconnected-(IC2A-X15-Pad16)") (class "Default")
      (node (ref "IC2") (pin "16") (pinfunction "X15_16") (pintype "input"))
    )
    (net (code "165") (name "unconnected-(IC3A-X10-Pad21)") (class "Default")
      (node (ref "IC3") (pin "21") (pinfunction "X10_21") (pintype "input"))
    )
    (net (code "166") (name "unconnected-(IC3A-X11-Pad20)") (class "Default")
      (node (ref "IC3") (pin "20") (pinfunction "X11_20") (pintype "input"))
    )
    (net (code "167") (name "unconnected-(IC3A-X12-Pad19)") (class "Default")
      (node (ref "IC3") (pin "19") (pinfunction "X12_19") (pintype "input"))
    )
    (net (code "168") (name "unconnected-(IC3A-X13-Pad18)") (class "Default")
      (node (ref "IC3") (pin "18") (pinfunction "X13_18") (pintype "input"))
    )
    (net (code "169") (name "unconnected-(IC3A-X14-Pad17)") (class "Default")
      (node (ref "IC3") (pin "17") (pinfunction "X14_17") (pintype "input"))
    )
    (net (code "170") (name "unconnected-(IC3A-X15-Pad16)") (class "Default")
      (node (ref "IC3") (pin "16") (pinfunction "X15_16") (pintype "input"))
    )
    (net (code "171") (name "unconnected-(IC4A-X10-Pad21)") (class "Default")
      (node (ref "IC4") (pin "21") (pinfunction "X10_21") (pintype "input"))
    )
    (net (code "172") (name "unconnected-(IC4A-X11-Pad20)") (class "Default")
      (node (ref "IC4") (pin "20") (pinfunction "X11_20") (pintype "input"))
    )
    (net (code "173") (name "unconnected-(IC4A-X12-Pad19)") (class "Default")
      (node (ref "IC4") (pin "19") (pinfunction "X12_19") (pintype "input"))
    )
    (net (code "174") (name "unconnected-(IC4A-X13-Pad18)") (class "Default")
      (node (ref "IC4") (pin "18") (pinfunction "X13_18") (pintype "input"))
    )
    (net (code "175") (name "unconnected-(IC4A-X14-Pad17)") (class "Default")
      (node (ref "IC4") (pin "17") (pinfunction "X14_17") (pintype "input"))
    )
    (net (code "176") (name "unconnected-(IC4A-X15-Pad16)") (class "Default")
      (node (ref "IC4") (pin "16") (pinfunction "X15_16") (pintype "input"))
    )
    (net (code "177") (name "unconnected-(IC5A-X10-Pad21)") (class "Default")
      (node (ref "IC5") (pin "21") (pinfunction "X10_21") (pintype "input"))
    )
    (net (code "178") (name "unconnected-(IC5A-X11-Pad20)") (class "Default")
      (node (ref "IC5") (pin "20") (pinfunction "X11_20") (pintype "input"))
    )
    (net (code "179") (name "unconnected-(IC5A-X12-Pad19)") (class "Default")
      (node (ref "IC5") (pin "19") (pinfunction "X12_19") (pintype "input"))
    )
    (net (code "180") (name "unconnected-(IC5A-X13-Pad18)") (class "Default")
      (node (ref "IC5") (pin "18") (pinfunction "X13_18") (pintype "input"))
    )
    (net (code "181") (name "unconnected-(IC5A-X14-Pad17)") (class "Default")
      (node (ref "IC5") (pin "17") (pinfunction "X14_17") (pintype "input"))
    )
    (net (code "182") (name "unconnected-(IC5A-X15-Pad16)") (class "Default")
      (node (ref "IC5") (pin "16") (pinfunction "X15_16") (pintype "input"))
    )
    (net (code "183") (name "unconnected-(MS0-S1-Pad2)") (class "Default")
      (node (ref "MS0") (pin "2") (pinfunction "S1_2") (pintype "passive"))
    )
    (net (code "184") (name "unconnected-(MS1-S1-Pad2)") (class "Default")
      (node (ref "MS1") (pin "2") (pinfunction "S1_2") (pintype "passive"))
    )
    (net (code "185") (name "unconnected-(MS2-S1-Pad2)") (class "Default")
      (node (ref "MS2") (pin "2") (pinfunction "S1_2") (pintype "passive"))
    )
    (net (code "186") (name "unconnected-(MS3-S1-Pad2)") (class "Default")
      (node (ref "MS3") (pin "2") (pinfunction "S1_2") (pintype "passive"))
    )
    (net (code "187") (name "unconnected-(MS4-S1-Pad2)") (class "Default")
      (node (ref "MS4") (pin "2") (pinfunction "S1_2") (pintype "passive"))
    )
    (net (code "188") (name "unconnected-(MS5-S1-Pad2)") (class "Default")
      (node (ref "MS5") (pin "2") (pinfunction "S1_2") (pintype "passive"))
    )
    (net (code "189") (name "unconnected-(MS6-S1-Pad2)") (class "Default")
      (node (ref "MS6") (pin "2") (pinfunction "S1_2") (pintype "passive"))
    )
    (net (code "190") (name "unconnected-(MS7-S1-Pad2)") (class "Default")
      (node (ref "MS7") (pin "2") (pinfunction "S1_2") (pintype "passive"))
    )
    (net (code "191") (name "unconnected-(MS8-S1-Pad2)") (class "Default")
      (node (ref "MS8") (pin "2") (pinfunction "S1_2") (pintype "passive"))
    )
    (net (code "192") (name "unconnected-(MS9-S1-Pad2)") (class "Default")
      (node (ref "MS9") (pin "2") (pinfunction "S1_2") (pintype "passive"))
    )
    (net (code "193") (name "unconnected-(SW0-S1-Pad2)") (class "Default")
      (node (ref "SW0") (pin "2") (pinfunction "S1_2") (pintype "passive"))
    )
    (net (code "194") (name "unconnected-(SW1-S1-Pad2)") (class "Default")
      (node (ref "SW1") (pin "2") (pinfunction "S1_2") (pintype "passive"))
    )
    (net (code "195") (name "unconnected-(SW2-S1-Pad2)") (class "Default")
      (node (ref "SW2") (pin "2") (pinfunction "S1_2") (pintype "passive"))
    )
    (net (code "196") (name "unconnected-(SW3-S1-Pad2)") (class "Default")
      (node (ref "SW3") (pin "2") (pinfunction "S1_2") (pintype "passive"))
    )
    (net (code "197") (name "unconnected-(SW4-S1-Pad2)") (class "Default")
      (node (ref "SW4") (pin "2") (pinfunction "S1_2") (pintype "passive"))
    )
    (net (code "198") (name "unconnected-(SW5-S1-Pad2)") (class "Default")
      (node (ref "SW5") (pin "2") (pinfunction "S1_2") (pintype "passive"))
    )
    (net (code "199") (name "unconnected-(SW6-S1-Pad2)") (class "Default")
      (node (ref "SW6") (pin "2") (pinfunction "S1_2") (pintype "passive"))
    )
    (net (code "200") (name "unconnected-(SW7-S1-Pad2)") (class "Default")
      (node (ref "SW7") (pin "2") (pinfunction "S1_2") (pintype "passive"))
    )
    (net (code "201") (name "unconnected-(SW8-S1-Pad2)") (class "Default")
      (node (ref "SW8") (pin "2") (pinfunction "S1_2") (pintype "passive"))
    )
    (net (code "202") (name "unconnected-(SW9-S1-Pad2)") (class "Default")
      (node (ref "SW9") (pin "2") (pinfunction "S1_2") (pintype "passive"))
    )
    (net (code "203") (name "unconnected-(U$1-5V-Pad+5V)") (class "Default")
      (node (ref "U$1") (pin "+5V") (pinfunction "5V_+5V") (pintype "bidirectional"))
    )
    (net (code "204") (name "unconnected-(U$1-Pad3V3-1)") (class "Default")
      (node (ref "U$1") (pin "3V3-1") (pinfunction "3V3-1_3V3-1") (pintype "bidirectional"))
    )
    (net (code "205") (name "unconnected-(U$1-Pad3V3-2)") (class "Default")
      (node (ref "U$1") (pin "3V3-2") (pinfunction "3V3-2_3V3-2") (pintype "bidirectional"))
    )
    (net (code "206") (name "unconnected-(U$1-PadD+)") (class "Default")
      (node (ref "U$1") (pin "D+") (pinfunction "D+_D+") (pintype "bidirectional"))
    )
    (net (code "207") (name "unconnected-(U$1-PadD-)") (class "Default")
      (node (ref "U$1") (pin "D-") (pinfunction "D-_D-") (pintype "bidirectional"))
    )
    (net (code "208") (name "unconnected-(U$1-PadDM)") (class "Default")
      (node (ref "U$1") (pin "DM") (pinfunction "DM_DM") (pintype "bidirectional"))
    )
    (net (code "209") (name "unconnected-(U$1-PadDP)") (class "Default")
      (node (ref "U$1") (pin "DP") (pinfunction "DP_DP") (pintype "bidirectional"))
    )
    (net (code "210") (name "unconnected-(U$1-PadG)") (class "Default")
      (node (ref "U$1") (pin "G") (pinfunction "G_G") (pintype "bidirectional"))
    )
    (net (code "211") (name "unconnected-(U$1-PadGND2)") (class "Default")
      (node (ref "U$1") (pin "GND2") (pinfunction "GND2_GND2") (pintype "bidirectional"))
    )
    (net (code "212") (name "unconnected-(U$1-PadGND3)") (class "Default")
      (node (ref "U$1") (pin "GND3") (pinfunction "GND3_GND3") (pintype "bidirectional"))
    )
    (net (code "213") (name "unconnected-(U$1-PadGND4)") (class "Default")
      (node (ref "U$1") (pin "GND4") (pinfunction "GND4_GND4") (pintype "bidirectional"))
    )
    (net (code "214") (name "unconnected-(U$1-PadGND5)") (class "Default")
      (node (ref "U$1") (pin "GND5") (pinfunction "GND5_GND5") (pintype "bidirectional"))
    )
    (net (code "215") (name "unconnected-(U$1-PadGND6)") (class "Default")
      (node (ref "U$1") (pin "GND6") (pinfunction "GND6_GND6") (pintype "bidirectional"))
    )
    (net (code "216") (name "unconnected-(U$1-PadLED)") (class "Default")
      (node (ref "U$1") (pin "LED") (pinfunction "LED_LED") (pintype "bidirectional"))
    )
    (net (code "217") (name "unconnected-(U$1-PadON{slash}OFF)") (class "Default")
      (node (ref "U$1") (pin "ON/OFF") (pinfunction "ON/OFF_ON/OFF") (pintype "bidirectional"))
    )
    (net (code "218") (name "unconnected-(U$1-PadPROGRAM)") (class "Default")
      (node (ref "U$1") (pin "PROGRAM") (pinfunction "PROGRAM_PROGRAM") (pintype "bidirectional"))
    )
    (net (code "219") (name "unconnected-(U$1-PadR+)") (class "Default")
      (node (ref "U$1") (pin "R+") (pinfunction "R+_R+") (pintype "bidirectional"))
    )
    (net (code "220") (name "unconnected-(U$1-PadR-)") (class "Default")
      (node (ref "U$1") (pin "R-") (pinfunction "R-_R-") (pintype "bidirectional"))
    )
    (net (code "221") (name "unconnected-(U$1-PadT+)") (class "Default")
      (node (ref "U$1") (pin "T+") (pinfunction "T+_T+") (pintype "bidirectional"))
    )
    (net (code "222") (name "unconnected-(U$1-PadT-)") (class "Default")
      (node (ref "U$1") (pin "T-") (pinfunction "T-_T-") (pintype "bidirectional"))
    )
    (net (code "223") (name "unconnected-(U$1-PadVBAT)") (class "Default")
      (node (ref "U$1") (pin "VBAT") (pinfunction "VBAT_VBAT") (pintype "bidirectional"))
    )
    (net (code "224") (name "unconnected-(U$1-PadVIN)") (class "Default")
      (node (ref "U$1") (pin "VIN") (pinfunction "VIN_VIN") (pintype "bidirectional"))
    )
    (net (code "225") (name "unconnected-(U$1-PadVUSB)") (class "Default")
      (node (ref "U$1") (pin "VUSB") (pinfunction "VUSB_VUSB") (pintype "bidirectional"))
    )
  )
)
